# EEG_Schematic.net
KiCad netlist of a schematic drawn in Altium Designer
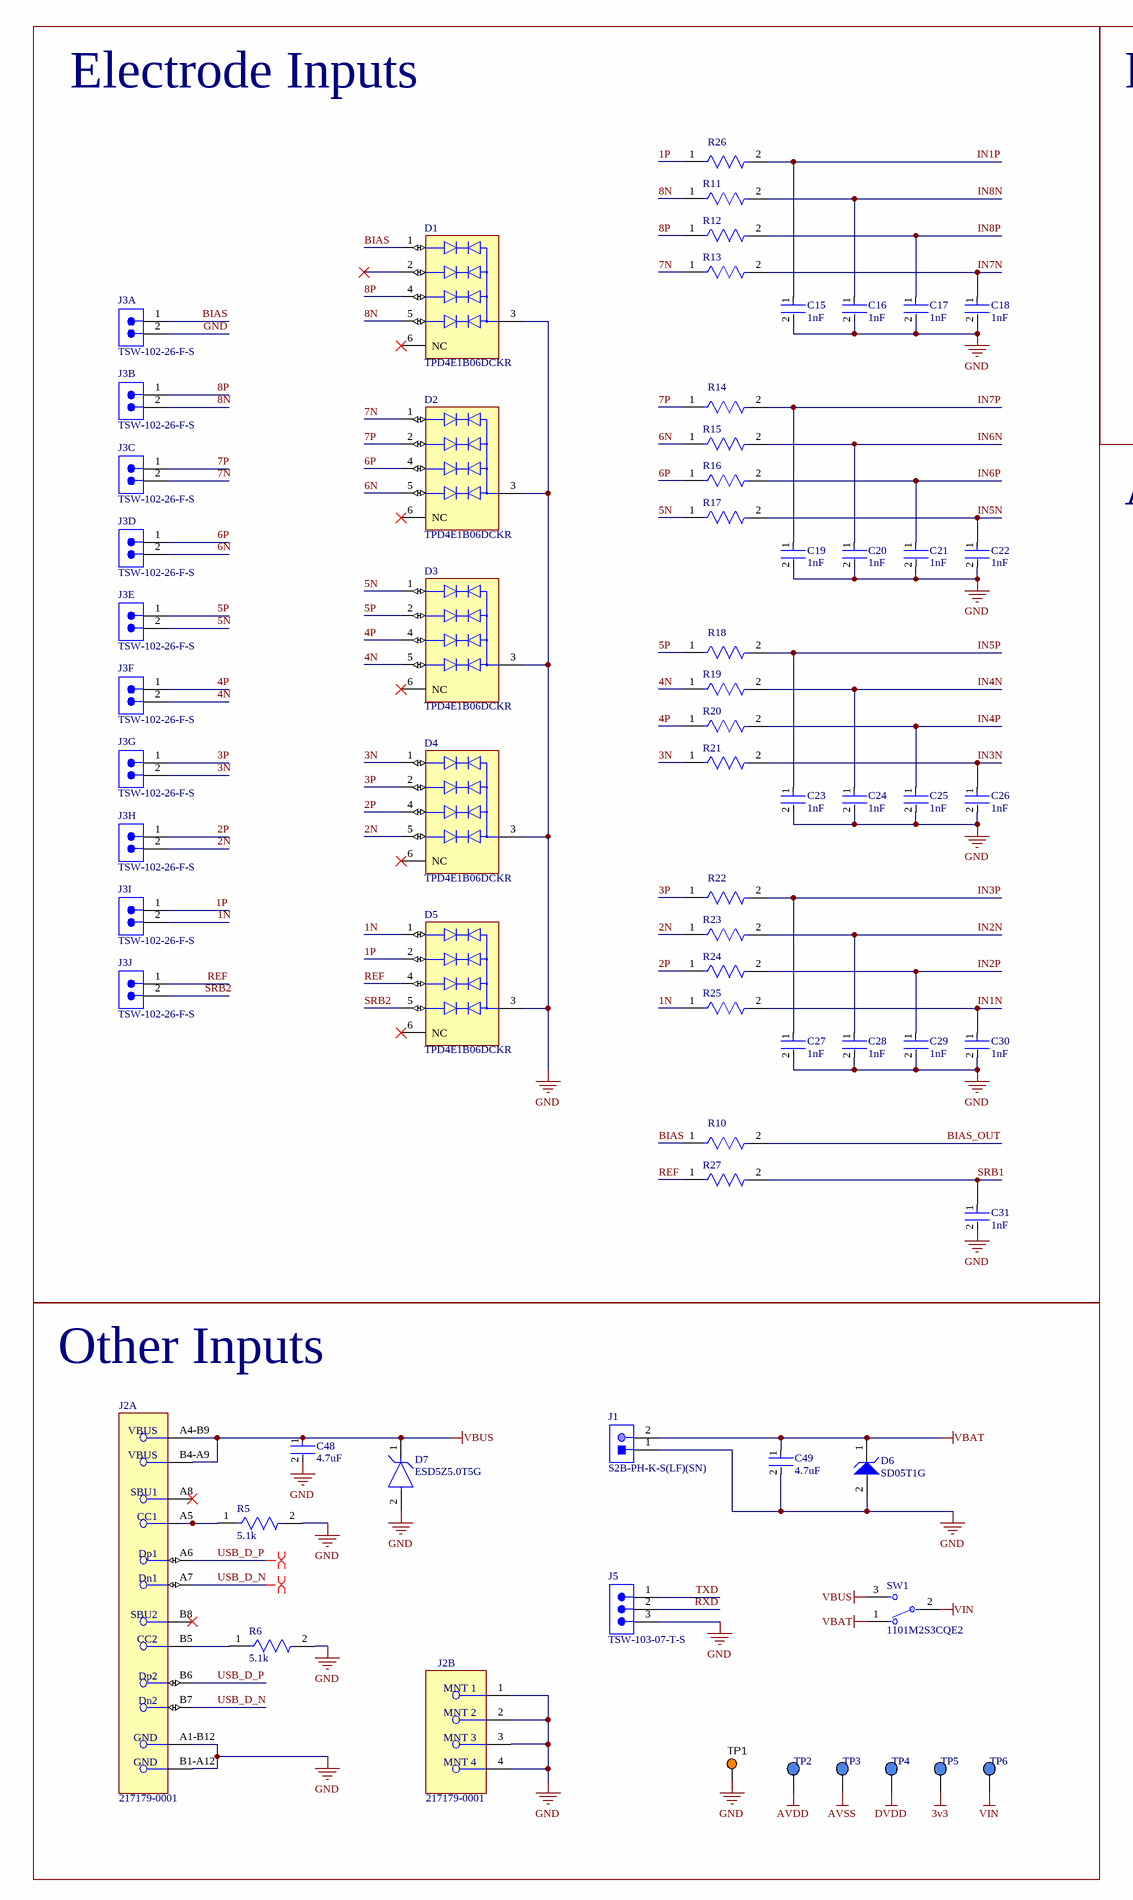
[diagram p0: EEG_Schematic.SchDoc, left]
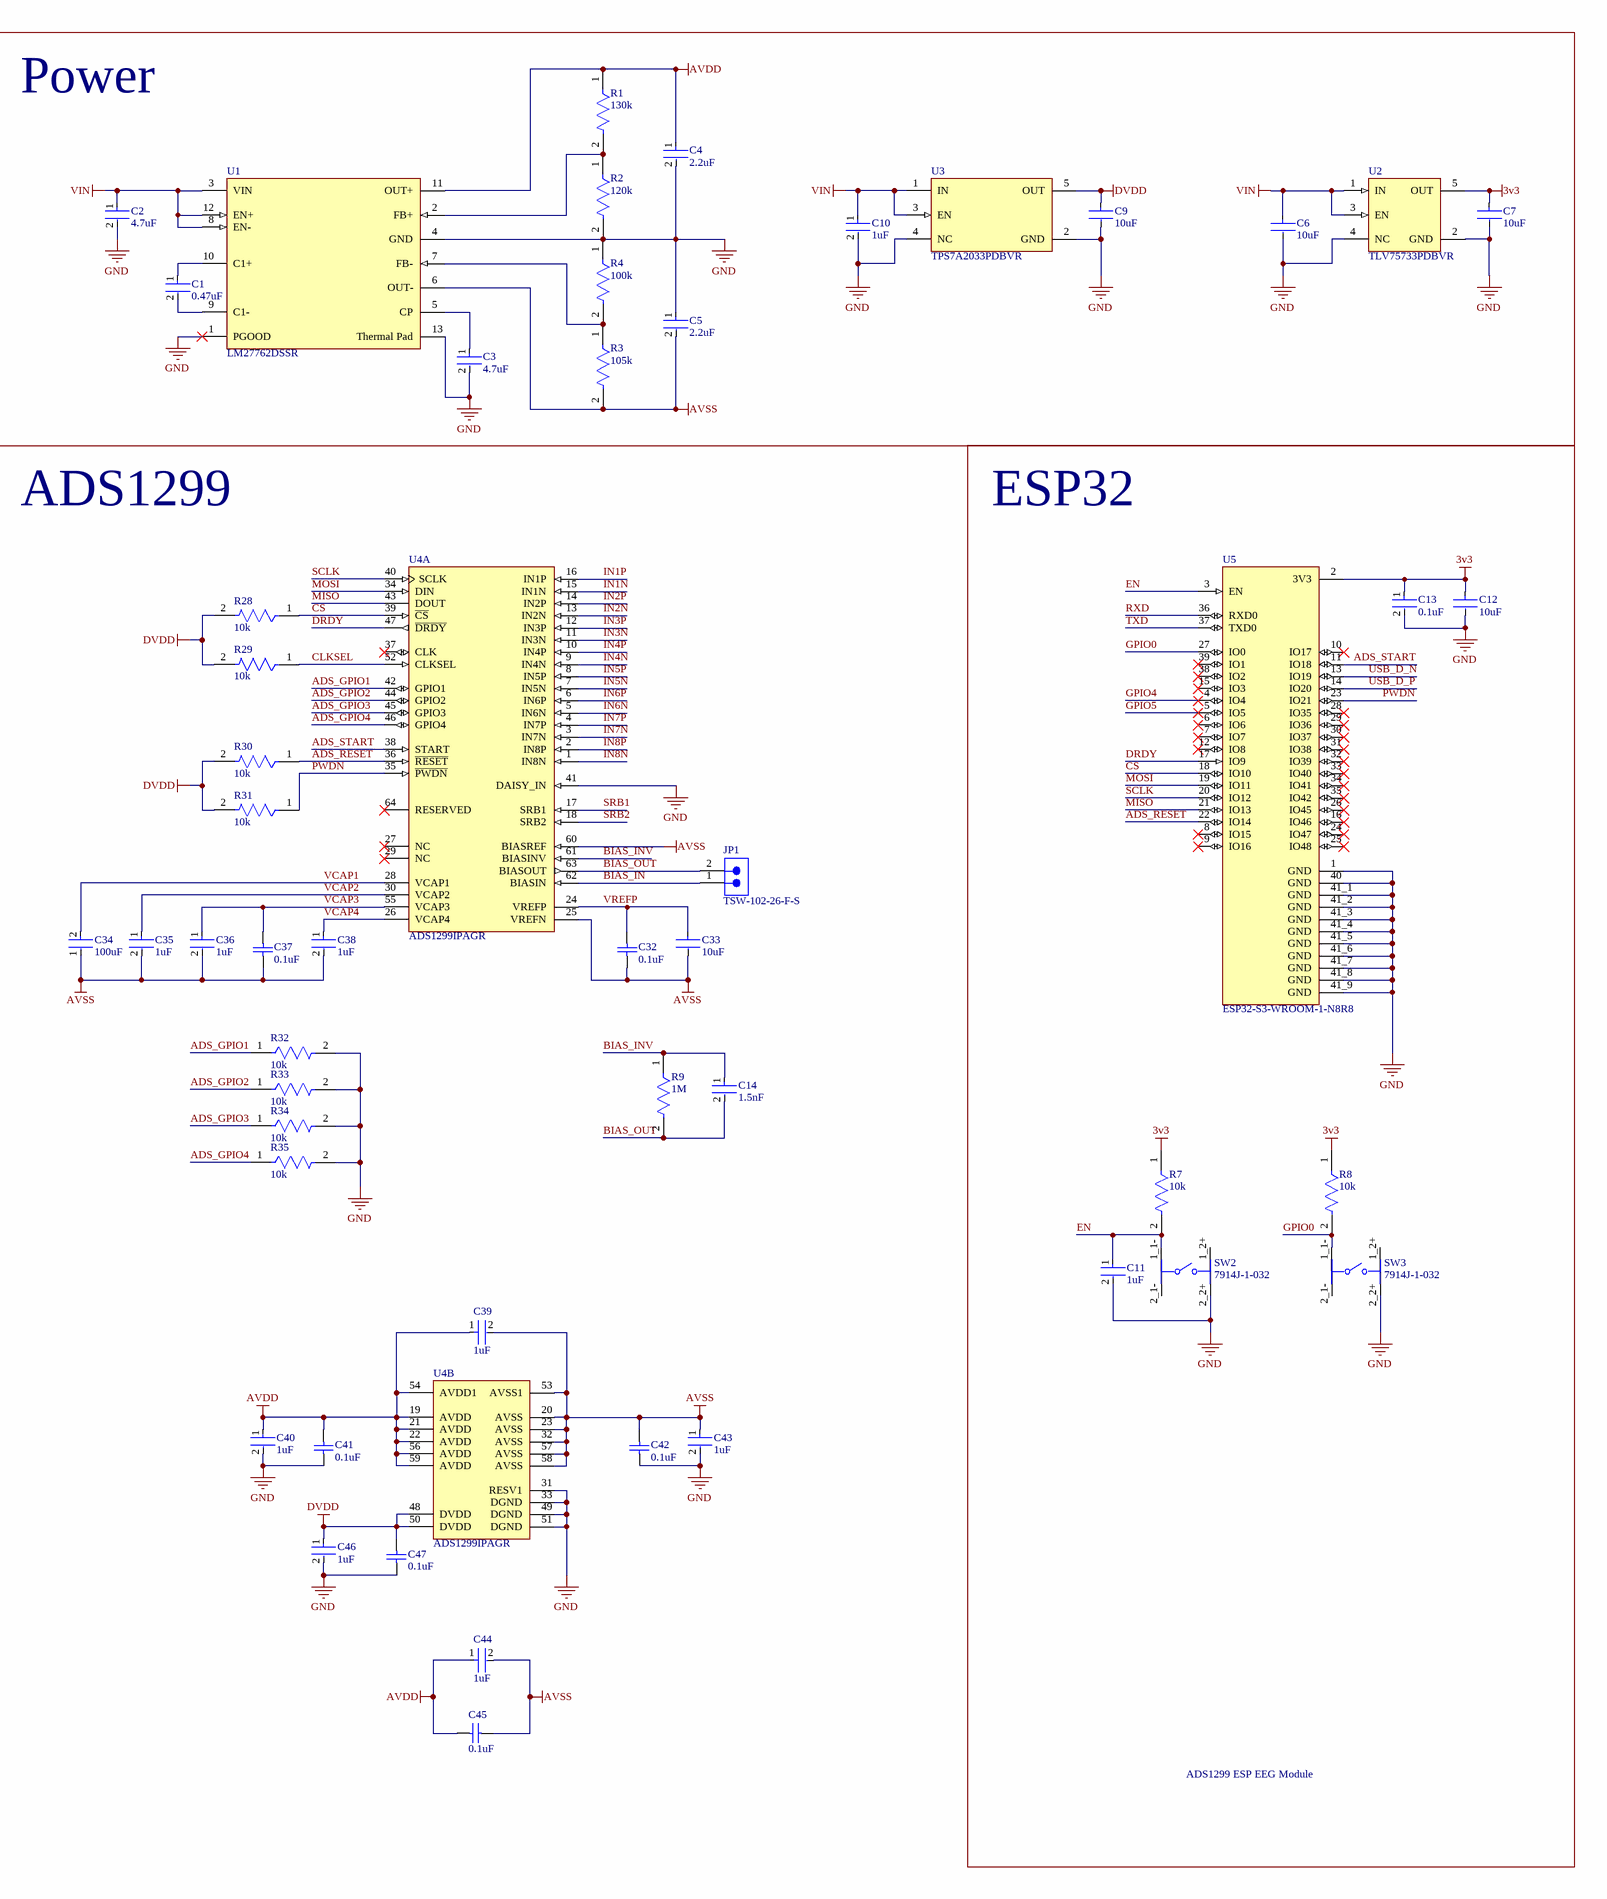
[diagram p1: EEG_Schematic.SchDoc, right]

(export (version "E")
  (design (tool "Eeschema 10.0.6"))
  (components
    (comp (ref "C1")
      (value "0.47uF")
      (footprint "FP-C0603C-CF-MFG")
      (description "Cap Ceramic 0.47uF 16V X7R 10% Pad SMD 0603 125C Automotive T/R")
      (fields (field (name "MANUFACTURER") "KEMET") (field (name "TOLERANCE") "0.1"))
      (libsource (lib "Altium Content Vault") (part "b4654b650e69147ec39a6b967a45e02"))
    )
    (comp (ref "C2")
      (value "4.7uF")
      (footprint "FP-GCJ21B-0_3-IPC_A")
      (description "Multilayer Ceramic Capacitors MLCC - SMD/SMT 0805 4.7uF 10%, 16VDC,  X7R 15%")
      (fields (field (name "TOLERANCE") "10%"))
      (libsource (lib "Altium Content Vault") (part "02cd4be3c70576c341d710602a673aa"))
    )
    (comp (ref "C3")
      (value "4.7uF")
      (footprint "FP-GCJ21B-0_3-IPC_A")
      (description "Multilayer Ceramic Capacitors MLCC - SMD/SMT 0805 4.7uF 10%, 16VDC,  X7R 15%")
      (fields (field (name "TOLERANCE") "10%"))
      (libsource (lib "Altium Content Vault") (part "02cd4be3c70576c341d710602a673aa"))
    )
    (comp (ref "C4")
      (value "2.2uF")
      (footprint "FP-GCM21B-0_15-IPC_B")
      (description "Ceramic Capacitor for Automotive 2.2uF ±10% 16VDC X7R 0805 Embossed T/R")
      (fields (field (name "TOLERANCE") "10%"))
      (libsource (lib "Altium Content Vault") (part "02cd4be3c70576c341d710602a673aa"))
    )
    (comp (ref "C5")
      (value "2.2uF")
      (footprint "FP-GCM21B-0_15-IPC_B")
      (description "Ceramic Capacitor for Automotive 2.2uF ±10% 16VDC X7R 0805 Embossed T/R")
      (fields (field (name "TOLERANCE") "10%"))
      (libsource (lib "Altium Content Vault") (part "02cd4be3c70576c341d710602a673aa"))
    )
    (comp (ref "C6")
      (value "10uF")
      (footprint "FP-GRJ21B-0_3-0_2-MFG")
      (description "CAP CER MLCC")
      (libsource (lib "") (part "11868f565c42a9108669ba33697ecf6_1"))
    )
    (comp (ref "C7")
      (value "10uF")
      (footprint "FP-GRJ21B-0_3-0_2-MFG")
      (description "CAP CER MLCC")
      (libsource (lib "") (part "11868f565c42a9108669ba33697ecf6_1"))
    )
    (comp (ref "C9")
      (value "10uF")
      (footprint "FP-GRJ21B-0_3-0_2-MFG")
      (description "CAP CER MLCC")
      (libsource (lib "") (part "11868f565c42a9108669ba33697ecf6_1"))
    )
    (comp (ref "C10")
      (value "1uF")
      (footprint "FP-CC0603-DA-MFG")
      (description "CAP CER 1UF 16V X7R 0603")
      (fields (field (name "TOLERANCE") "0.1") (field (name "MANUFACTURER") "YAGEO"))
      (libsource (lib "Altium Content Vault") (part "11868f565c42a9108669ba33697ecf6"))
    )
    (comp (ref "C11")
      (value "1uF")
      (footprint "FP-CC0603-DA-MFG")
      (description "CAP CER 1UF 16V X7R 0603")
      (fields (field (name "TOLERANCE") "0.1") (field (name "MANUFACTURER") "YAGEO"))
      (libsource (lib "Altium Content Vault") (part "11868f565c42a9108669ba33697ecf6"))
    )
    (comp (ref "C12")
      (value "10uF")
      (footprint "FP-GRJ21B-0_3-0_2-MFG")
      (description "CAP CER MLCC")
      (libsource (lib "") (part "11868f565c42a9108669ba33697ecf6_1"))
    )
    (comp (ref "C13")
      (value "0.1uF")
      (footprint "FP-CGA3E-0_3-0_1-MFG")
      (description "Cap Ceramic 100nF 50V X7R 10% Pad SMD 0603 +125°C Automotive T/R")
      (fields (field (name "TOLERANCE") "10%"))
      (libsource (lib "Altium Content Vault") (part "b4654b650e69147ec39a6b967a45e02"))
    )
    (comp (ref "C14")
      (value "1.5nF")
      (footprint "FP-C0603C-CF-MFG")
      (description "CAP CER 1500PF 100V NP0 0603")
      (fields
        (field (name "MANUFACTURER PART NUMBER") "C0603C152J1GACTU")
        (field (name "OCTOPART") "https://octopart.com/c0603c152j1gactu-kemet-12793172")
      )
      (libsource (lib "Altium Content Vault") (part "b4654b650e69147ec39a6b967a45e02"))
    )
    (comp (ref "C15")
      (value "1nF")
      (footprint "FP-C0603C-CF-MFG")
      (description "CAP CER 1000PF 50V 1% NP0 0603")
      (fields (field (name "TOLERANCE") "0.01") (field (name "MANUFACTURER PART NUMBER") "C0603C102F5GACTU"))
      (libsource (lib "Altium Content Vault") (part "b4654b650e69147ec39a6b967a45e02"))
    )
    (comp (ref "C16")
      (value "1nF")
      (footprint "FP-C0603C-CF-MFG")
      (description "CAP CER 1000PF 50V 1% NP0 0603")
      (fields (field (name "TOLERANCE") "0.01") (field (name "MANUFACTURER PART NUMBER") "C0603C102F5GACTU"))
      (libsource (lib "Altium Content Vault") (part "b4654b650e69147ec39a6b967a45e02"))
    )
    (comp (ref "C17")
      (value "1nF")
      (footprint "FP-C0603C-CF-MFG")
      (description "CAP CER 1000PF 50V 1% NP0 0603")
      (fields (field (name "TOLERANCE") "0.01") (field (name "MANUFACTURER PART NUMBER") "C0603C102F5GACTU"))
      (libsource (lib "Altium Content Vault") (part "b4654b650e69147ec39a6b967a45e02"))
    )
    (comp (ref "C18")
      (value "1nF")
      (footprint "FP-C0603C-CF-MFG")
      (description "CAP CER 1000PF 50V 1% NP0 0603")
      (fields (field (name "TOLERANCE") "0.01") (field (name "MANUFACTURER PART NUMBER") "C0603C102F5GACTU"))
      (libsource (lib "Altium Content Vault") (part "b4654b650e69147ec39a6b967a45e02"))
    )
    (comp (ref "C19")
      (value "1nF")
      (footprint "FP-C0603C-CF-MFG")
      (description "CAP CER 1000PF 50V 1% NP0 0603")
      (fields (field (name "TOLERANCE") "0.01") (field (name "MANUFACTURER PART NUMBER") "C0603C102F5GACTU"))
      (libsource (lib "Altium Content Vault") (part "b4654b650e69147ec39a6b967a45e02"))
    )
    (comp (ref "C20")
      (value "1nF")
      (footprint "FP-C0603C-CF-MFG")
      (description "CAP CER 1000PF 50V 1% NP0 0603")
      (fields (field (name "TOLERANCE") "0.01") (field (name "MANUFACTURER PART NUMBER") "C0603C102F5GACTU"))
      (libsource (lib "Altium Content Vault") (part "b4654b650e69147ec39a6b967a45e02"))
    )
    (comp (ref "C21")
      (value "1nF")
      (footprint "FP-C0603C-CF-MFG")
      (description "CAP CER 1000PF 50V 1% NP0 0603")
      (fields (field (name "TOLERANCE") "0.01") (field (name "MANUFACTURER PART NUMBER") "C0603C102F5GACTU"))
      (libsource (lib "Altium Content Vault") (part "b4654b650e69147ec39a6b967a45e02"))
    )
    (comp (ref "C22")
      (value "1nF")
      (footprint "FP-C0603C-CF-MFG")
      (description "CAP CER 1000PF 50V 1% NP0 0603")
      (fields (field (name "TOLERANCE") "0.01") (field (name "MANUFACTURER PART NUMBER") "C0603C102F5GACTU"))
      (libsource (lib "Altium Content Vault") (part "b4654b650e69147ec39a6b967a45e02"))
    )
    (comp (ref "C23")
      (value "1nF")
      (footprint "FP-C0603C-CF-MFG")
      (description "CAP CER 1000PF 50V 1% NP0 0603")
      (fields (field (name "TOLERANCE") "0.01") (field (name "MANUFACTURER PART NUMBER") "C0603C102F5GACTU"))
      (libsource (lib "Altium Content Vault") (part "b4654b650e69147ec39a6b967a45e02"))
    )
    (comp (ref "C24")
      (value "1nF")
      (footprint "FP-C0603C-CF-MFG")
      (description "CAP CER 1000PF 50V 1% NP0 0603")
      (fields (field (name "TOLERANCE") "0.01") (field (name "MANUFACTURER PART NUMBER") "C0603C102F5GACTU"))
      (libsource (lib "Altium Content Vault") (part "b4654b650e69147ec39a6b967a45e02"))
    )
    (comp (ref "C25")
      (value "1nF")
      (footprint "FP-C0603C-CF-MFG")
      (description "CAP CER 1000PF 50V 1% NP0 0603")
      (fields (field (name "TOLERANCE") "0.01") (field (name "MANUFACTURER PART NUMBER") "C0603C102F5GACTU"))
      (libsource (lib "Altium Content Vault") (part "b4654b650e69147ec39a6b967a45e02"))
    )
    (comp (ref "C26")
      (value "1nF")
      (footprint "FP-C0603C-CF-MFG")
      (description "CAP CER 1000PF 50V 1% NP0 0603")
      (fields (field (name "TOLERANCE") "0.01") (field (name "MANUFACTURER PART NUMBER") "C0603C102F5GACTU"))
      (libsource (lib "Altium Content Vault") (part "b4654b650e69147ec39a6b967a45e02"))
    )
    (comp (ref "C27")
      (value "1nF")
      (footprint "FP-C0603C-CF-MFG")
      (description "CAP CER 1000PF 50V 1% NP0 0603")
      (fields (field (name "TOLERANCE") "0.01") (field (name "MANUFACTURER PART NUMBER") "C0603C102F5GACTU"))
      (libsource (lib "Altium Content Vault") (part "b4654b650e69147ec39a6b967a45e02"))
    )
    (comp (ref "C28")
      (value "1nF")
      (footprint "FP-C0603C-CF-MFG")
      (description "CAP CER 1000PF 50V 1% NP0 0603")
      (fields (field (name "TOLERANCE") "0.01") (field (name "MANUFACTURER PART NUMBER") "C0603C102F5GACTU"))
      (libsource (lib "Altium Content Vault") (part "b4654b650e69147ec39a6b967a45e02"))
    )
    (comp (ref "C29")
      (value "1nF")
      (footprint "FP-C0603C-CF-MFG")
      (description "CAP CER 1000PF 50V 1% NP0 0603")
      (fields (field (name "TOLERANCE") "0.01") (field (name "MANUFACTURER PART NUMBER") "C0603C102F5GACTU"))
      (libsource (lib "Altium Content Vault") (part "b4654b650e69147ec39a6b967a45e02"))
    )
    (comp (ref "C30")
      (value "1nF")
      (footprint "FP-C0603C-CF-MFG")
      (description "CAP CER 1000PF 50V 1% NP0 0603")
      (fields (field (name "TOLERANCE") "0.01") (field (name "MANUFACTURER PART NUMBER") "C0603C102F5GACTU"))
      (libsource (lib "Altium Content Vault") (part "b4654b650e69147ec39a6b967a45e02"))
    )
    (comp (ref "C31")
      (value "1nF")
      (footprint "FP-C0603C-CF-MFG")
      (description "CAP CER 1000PF 50V 1% NP0 0603")
      (fields (field (name "TOLERANCE") "0.01") (field (name "MANUFACTURER PART NUMBER") "C0603C102F5GACTU"))
      (libsource (lib "Altium Content Vault") (part "b4654b650e69147ec39a6b967a45e02"))
    )
    (comp (ref "C32")
      (value "0.1uF")
      (footprint "CAPC1608X87X45LL20T05")
      (fields (field (name "PART NUMBER") "C0603X104J4RACTU") (field (name "MANUFACTURER") "Kemet"))
      (libsource (lib "Altium Content Vault") (part "CAP"))
    )
    (comp (ref "C33")
      (value "10uF")
      (footprint "FP-GRJ21B-0_3-0_2-MFG")
      (description "CAP CER MLCC")
      (libsource (lib "") (part "11868f565c42a9108669ba33697ecf6_1"))
    )
    (comp (ref "C34")
      (value "100uF")
      (footprint "FP-GRM31C-0_3-e0_3_0_8-IPC_B")
      (description "Chip Multilayer Ceramic Capacitors for General Purpose, 1206, 100uF, X5R, 15%, 20%, 10V")
      (libsource (lib "Altium Content Vault") (part "f23184f103b6ebe33a8c269c53dcba6"))
    )
    (comp (ref "C35")
      (value "1uF")
      (footprint "FP-CC0603-DA-MFG")
      (description "CAP CER 1UF 16V X7R 0603")
      (fields (field (name "TOLERANCE") "0.1") (field (name "MANUFACTURER") "YAGEO"))
      (libsource (lib "Altium Content Vault") (part "11868f565c42a9108669ba33697ecf6"))
    )
    (comp (ref "C36")
      (value "1uF")
      (footprint "FP-CC0603-DA-MFG")
      (description "CAP CER 1UF 16V X7R 0603")
      (fields (field (name "TOLERANCE") "0.1") (field (name "MANUFACTURER") "YAGEO"))
      (libsource (lib "Altium Content Vault") (part "11868f565c42a9108669ba33697ecf6"))
    )
    (comp (ref "C37")
      (value "0.1uF")
      (footprint "CAPC1608X87X45LL20T05")
      (fields (field (name "PART NUMBER") "C0603X104J4RACTU") (field (name "MANUFACTURER") "Kemet"))
      (libsource (lib "Altium Content Vault") (part "CAP"))
    )
    (comp (ref "C38")
      (value "1uF")
      (footprint "FP-CC0603-DA-MFG")
      (description "CAP CER 1UF 16V X7R 0603")
      (fields (field (name "TOLERANCE") "0.1") (field (name "MANUFACTURER") "YAGEO"))
      (libsource (lib "Altium Content Vault") (part "11868f565c42a9108669ba33697ecf6"))
    )
    (comp (ref "C39")
      (value "1uF")
      (footprint "FP-CC0603-DA-MFG")
      (description "CAP CER 1UF 16V X7R 0603")
      (fields (field (name "TOLERANCE") "0.1") (field (name "MANUFACTURER") "YAGEO"))
      (libsource (lib "Altium Content Vault") (part "11868f565c42a9108669ba33697ecf6"))
    )
    (comp (ref "C40")
      (value "1uF")
      (footprint "FP-CC0603-DA-MFG")
      (description "CAP CER 1UF 16V X7R 0603")
      (fields (field (name "TOLERANCE") "0.1") (field (name "MANUFACTURER") "YAGEO"))
      (libsource (lib "Altium Content Vault") (part "11868f565c42a9108669ba33697ecf6"))
    )
    (comp (ref "C41")
      (value "0.1uF")
      (footprint "CAPC1608X87X45LL20T05")
      (fields (field (name "PART NUMBER") "C0603X104J4RACTU") (field (name "MANUFACTURER") "Kemet"))
      (libsource (lib "Altium Content Vault") (part "CAP"))
    )
    (comp (ref "C42")
      (value "0.1uF")
      (footprint "CAPC1608X87X45LL20T05")
      (fields (field (name "PART NUMBER") "C0603X104J4RACTU") (field (name "MANUFACTURER") "Kemet"))
      (libsource (lib "Altium Content Vault") (part "CAP"))
    )
    (comp (ref "C43")
      (value "1uF")
      (footprint "FP-CC0603-DA-MFG")
      (description "CAP CER 1UF 16V X7R 0603")
      (fields (field (name "TOLERANCE") "0.1") (field (name "MANUFACTURER") "YAGEO"))
      (libsource (lib "Altium Content Vault") (part "11868f565c42a9108669ba33697ecf6"))
    )
    (comp (ref "C44")
      (value "1uF")
      (footprint "FP-CC0603-DA-MFG")
      (description "CAP CER 1UF 16V X7R 0603")
      (fields (field (name "TOLERANCE") "0.1") (field (name "MANUFACTURER") "YAGEO"))
      (libsource (lib "Altium Content Vault") (part "11868f565c42a9108669ba33697ecf6"))
    )
    (comp (ref "C45")
      (value "0.1uF")
      (footprint "CAPC1608X87X45LL20T05")
      (fields (field (name "PART NUMBER") "C0603X104J4RACTU") (field (name "MANUFACTURER") "Kemet"))
      (libsource (lib "Altium Content Vault") (part "CAP"))
    )
    (comp (ref "C46")
      (value "1uF")
      (footprint "FP-CC0603-DA-MFG")
      (description "CAP CER 1UF 16V X7R 0603")
      (fields (field (name "TOLERANCE") "0.1") (field (name "MANUFACTURER") "YAGEO"))
      (libsource (lib "Altium Content Vault") (part "11868f565c42a9108669ba33697ecf6"))
    )
    (comp (ref "C47")
      (value "0.1uF")
      (footprint "CAPC1608X87X45LL20T05")
      (fields (field (name "PART NUMBER") "C0603X104J4RACTU") (field (name "MANUFACTURER") "Kemet"))
      (libsource (lib "Altium Content Vault") (part "CAP"))
    )
    (comp (ref "C48")
      (value "4.7uF")
      (footprint "FP-GCJ21B-0_3-IPC_A")
      (description "Multilayer Ceramic Capacitors MLCC - SMD/SMT 0805 4.7uF 10%, 16VDC,  X7R 15%")
      (fields (field (name "TOLERANCE") "10%"))
      (libsource (lib "Altium Content Vault") (part "02cd4be3c70576c341d710602a673aa"))
    )
    (comp (ref "C49")
      (value "4.7uF")
      (footprint "FP-GCJ21B-0_3-IPC_A")
      (description "Multilayer Ceramic Capacitors MLCC - SMD/SMT 0805 4.7uF 10%, 16VDC,  X7R 15%")
      (fields (field (name "TOLERANCE") "10%"))
      (libsource (lib "Altium Content Vault") (part "02cd4be3c70576c341d710602a673aa"))
    )
    (comp (ref "D1")
      (value "TPD4E1B06DCKR")
      (footprint "TVS_TPD4E1B06DCKR")
      (description "Quad 0.7-pF, Â±5.5-V, Â±12-kV ESD protection diode with 0.5-nA max leakage in SOT & SC70 packages")
      (fields (field (name "MF") "Texas Instruments"))
      (libsource (lib "TPD4E1B06DCKR") (part "TPD4E1B06DCKR"))
    )
    (comp (ref "D2")
      (value "TPD4E1B06DCKR")
      (footprint "TVS_TPD4E1B06DCKR")
      (description "Quad 0.7-pF, Â±5.5-V, Â±12-kV ESD protection diode with 0.5-nA max leakage in SOT & SC70 packages")
      (fields (field (name "MF") "Texas Instruments"))
      (libsource (lib "TPD4E1B06DCKR") (part "TPD4E1B06DCKR"))
    )
    (comp (ref "D3")
      (value "TPD4E1B06DCKR")
      (footprint "TVS_TPD4E1B06DCKR")
      (description "Quad 0.7-pF, Â±5.5-V, Â±12-kV ESD protection diode with 0.5-nA max leakage in SOT & SC70 packages")
      (fields (field (name "MF") "Texas Instruments"))
      (libsource (lib "TPD4E1B06DCKR") (part "TPD4E1B06DCKR"))
    )
    (comp (ref "D4")
      (value "TPD4E1B06DCKR")
      (footprint "TVS_TPD4E1B06DCKR")
      (description "Quad 0.7-pF, Â±5.5-V, Â±12-kV ESD protection diode with 0.5-nA max leakage in SOT & SC70 packages")
      (fields (field (name "MF") "Texas Instruments"))
      (libsource (lib "TPD4E1B06DCKR") (part "TPD4E1B06DCKR"))
    )
    (comp (ref "D5")
      (value "TPD4E1B06DCKR")
      (footprint "TVS_TPD4E1B06DCKR")
      (description "Quad 0.7-pF, Â±5.5-V, Â±12-kV ESD protection diode with 0.5-nA max leakage in SOT & SC70 packages")
      (fields (field (name "MF") "Texas Instruments"))
      (libsource (lib "TPD4E1B06DCKR") (part "TPD4E1B06DCKR"))
    )
    (comp (ref "D6")
      (value "SD05T1G")
      (footprint "ONSC-SOD-323-2-477-02_G_V")
      (description "Transient Voltage Suppressor Diode, for ESD Protection, 2-Pin SOD-323, Pb-Free, Tape and Reel")
      (fields (field (name "MANUFACTURER") "On Semiconductor"))
      (libsource (lib "Altium Content Vault") (part "ONSC-K1A2-2"))
    )
    (comp (ref "D7")
      (value "ESD5Z5.0T5G")
      (footprint "FP-502-01-MFG")
      (description "ESD5Z5.0T5G Trans Voltage Suppressor Diode, 174W, 5V V(RWM), Unidirectional, 1 Element, Silicon")
      (libsource (lib "Altium Content Vault") (part "d9da4cfb8af32e832502365dfa3d88e"))
    )
    (comp (ref "J1")
      (value "S2B-PH-K-S(LF)(SN)")
      (footprint "JST-S2B-PH-K-S_V")
      (fields (field (name "TOLERANCE") "20%"))
      (libsource (lib "Altium Content Vault") (part "CN-1P-M-R2"))
    )
    (comp (ref "J2")
      (value "217179-0001")
      (footprint "FP-2171790001-MFG")
      (description "CONN RCP USB2.0 TYP C 24P SMD RA")
      (libsource (lib "Altium Content Vault") (part "8b86497a633d14b3f74642136fc0ce6"))
    )
    (comp (ref "J3A")
      (value "TSW-102-26-F-S")
      (footprint "SMTC-TSW-102-26-XX-S")
      (description "0.025\" SQ Post Header, Through-hole, Vertical, -55 to 125 degC, 2.54 mm Pitch, 2-Pin, Male, RoHS")
      (fields (field (name "MANUFACTURER") "Samtec"))
      (libsource (lib "Altium Content Vault") (part "SMTC-TSW-102-X-X-S-X"))
    )
    (comp (ref "J3B")
      (value "TSW-102-26-F-S")
      (footprint "SMTC-TSW-102-26-XX-S")
      (description "0.025\" SQ Post Header, Through-hole, Vertical, -55 to 125 degC, 2.54 mm Pitch, 2-Pin, Male, RoHS")
      (fields (field (name "MANUFACTURER") "Samtec"))
      (libsource (lib "Altium Content Vault") (part "SMTC-TSW-102-X-X-S-X"))
    )
    (comp (ref "J3C")
      (value "TSW-102-26-F-S")
      (footprint "SMTC-TSW-102-26-XX-S")
      (description "0.025\" SQ Post Header, Through-hole, Vertical, -55 to 125 degC, 2.54 mm Pitch, 2-Pin, Male, RoHS")
      (fields (field (name "MANUFACTURER") "Samtec"))
      (libsource (lib "Altium Content Vault") (part "SMTC-TSW-102-X-X-S-X"))
    )
    (comp (ref "J3D")
      (value "TSW-102-26-F-S")
      (footprint "SMTC-TSW-102-26-XX-S")
      (description "0.025\" SQ Post Header, Through-hole, Vertical, -55 to 125 degC, 2.54 mm Pitch, 2-Pin, Male, RoHS")
      (fields (field (name "MANUFACTURER") "Samtec"))
      (libsource (lib "Altium Content Vault") (part "SMTC-TSW-102-X-X-S-X"))
    )
    (comp (ref "J3E")
      (value "TSW-102-26-F-S")
      (footprint "SMTC-TSW-102-26-XX-S")
      (description "0.025\" SQ Post Header, Through-hole, Vertical, -55 to 125 degC, 2.54 mm Pitch, 2-Pin, Male, RoHS")
      (fields (field (name "MANUFACTURER") "Samtec"))
      (libsource (lib "Altium Content Vault") (part "SMTC-TSW-102-X-X-S-X"))
    )
    (comp (ref "J3F")
      (value "TSW-102-26-F-S")
      (footprint "SMTC-TSW-102-26-XX-S")
      (description "0.025\" SQ Post Header, Through-hole, Vertical, -55 to 125 degC, 2.54 mm Pitch, 2-Pin, Male, RoHS")
      (fields (field (name "MANUFACTURER") "Samtec"))
      (libsource (lib "Altium Content Vault") (part "SMTC-TSW-102-X-X-S-X"))
    )
    (comp (ref "J3G")
      (value "TSW-102-26-F-S")
      (footprint "SMTC-TSW-102-26-XX-S")
      (description "0.025\" SQ Post Header, Through-hole, Vertical, -55 to 125 degC, 2.54 mm Pitch, 2-Pin, Male, RoHS")
      (fields (field (name "MANUFACTURER") "Samtec"))
      (libsource (lib "Altium Content Vault") (part "SMTC-TSW-102-X-X-S-X"))
    )
    (comp (ref "J3H")
      (value "TSW-102-26-F-S")
      (footprint "SMTC-TSW-102-26-XX-S")
      (description "0.025\" SQ Post Header, Through-hole, Vertical, -55 to 125 degC, 2.54 mm Pitch, 2-Pin, Male, RoHS")
      (fields (field (name "MANUFACTURER") "Samtec"))
      (libsource (lib "Altium Content Vault") (part "SMTC-TSW-102-X-X-S-X"))
    )
    (comp (ref "J3I")
      (value "TSW-102-26-F-S")
      (footprint "SMTC-TSW-102-26-XX-S")
      (description "0.025\" SQ Post Header, Through-hole, Vertical, -55 to 125 degC, 2.54 mm Pitch, 2-Pin, Male, RoHS")
      (fields (field (name "MANUFACTURER") "Samtec"))
      (libsource (lib "Altium Content Vault") (part "SMTC-TSW-102-X-X-S-X"))
    )
    (comp (ref "J3J")
      (value "TSW-102-26-F-S")
      (footprint "SMTC-TSW-102-26-XX-S")
      (description "0.025\" SQ Post Header, Through-hole, Vertical, -55 to 125 degC, 2.54 mm Pitch, 2-Pin, Male, RoHS")
      (fields (field (name "MANUFACTURER") "Samtec"))
      (libsource (lib "Altium Content Vault") (part "SMTC-TSW-102-X-X-S-X"))
    )
    (comp (ref "J5")
      (value "TSW-103-07-T-S")
      (footprint "SMTC-TSW-103-07-X-S")
      (description "0.025\" SQ Post Header, Through-hole, Vertical, -55 to 105 degC, 2.54 mm Pitch, 3-Pin, Male, RoHS")
      (fields (field (name "MANUFACTURER") "Samtec"))
      (libsource (lib "Altium Content Vault") (part "SMTC-TSW-103-X-X-S-X"))
    )
    (comp (ref "JP1")
      (value "TSW-102-26-F-S")
      (footprint "SMTC-TSW-102-26-XX-S")
      (description "0.025\" SQ Post Header, Through-hole, Vertical, -55 to 125 degC, 2.54 mm Pitch, 2-Pin, Male, RoHS")
      (fields (field (name "MANUFACTURER") "Samtec"))
      (libsource (lib "Altium Content Vault") (part "SMTC-TSW-102-X-X-S-X"))
    )
    (comp (ref "R1")
      (value "130k")
      (footprint "FP-MCT0603-IPC_B")
      (description "RES SMD 100 OHM 1% 1/8W 0603")
      (fields (field (name "TOLERANCE") "0.1%"))
      (libsource (lib "Altium Content Vault") (part "1029c3af85768c4190bb7ad29bc67b5"))
    )
    (comp (ref "R2")
      (value "120k")
      (footprint "FP-RT0603-MFG")
      (description "RES SMD 120K OHM 0.1% 1/10W 0603")
      (fields (field (name "TOLERANCE") "0.001") (field (name "MANUFACTURER") "Yageo"))
      (libsource (lib "Altium Content Vault") (part "1029c3af85768c4190bb7ad29bc67b5"))
    )
    (comp (ref "R3")
      (value "105k")
      (footprint "FP-RT0603-MFG")
      (description "RES SMD 105K OHM 0.1% 1/10W 0603")
      (fields
        (field (name "MANUFACTURER PART NUMBER") "RT0603BRD07105KL")
        (field (name "OCTOPART") "https://octopart.com/rt0603brd07105kl-yageo-1216175")
      )
      (libsource (lib "Altium Content Vault") (part "1029c3af85768c4190bb7ad29bc67b5"))
    )
    (comp (ref "R4")
      (value "100k")
      (footprint "FP-AT0603-IPC_A")
      (description "Thin Film Chip Resistors Automotive Grade 100kΩ 0.1% 25ppm/°C 0603")
      (fields (field (name "TOLERANCE") "0.1%"))
      (libsource (lib "Altium Content Vault") (part "1029c3af85768c4190bb7ad29bc67b5"))
    )
    (comp (ref "R5")
      (value "5.1k")
      (footprint "FP-RT0603-MFG")
      (description "RES SMD 5.1K OHM 1% 1/10W 0603")
      (fields
        (field (name "MANUFACTURER") "Yageo")
        (field (name "OCTOPART") "https://octopart.com/rt0603fre075k1l-yageo-1421390")
      )
      (libsource (lib "Altium Content Vault") (part "1029c3af85768c4190bb7ad29bc67b5"))
    )
    (comp (ref "R6")
      (value "5.1k")
      (footprint "FP-RT0603-MFG")
      (description "RES SMD 5.1K OHM 1% 1/10W 0603")
      (fields
        (field (name "MANUFACTURER") "Yageo")
        (field (name "OCTOPART") "https://octopart.com/rt0603fre075k1l-yageo-1421390")
      )
      (libsource (lib "Altium Content Vault") (part "1029c3af85768c4190bb7ad29bc67b5"))
    )
    (comp (ref "R7")
      (value "10k")
      (footprint "FP-AC0603-MFG")
      (description "RES 10kΩ 1.00% 0.2W 0603")
      (libsource (lib "Altium Content Vault") (part "1029c3af85768c4190bb7ad29bc67b5"))
    )
    (comp (ref "R8")
      (value "10k")
      (footprint "FP-AC0603-MFG")
      (description "RES 10kΩ 1.00% 0.2W 0603")
      (libsource (lib "Altium Content Vault") (part "1029c3af85768c4190bb7ad29bc67b5"))
    )
    (comp (ref "R9")
      (value "1M")
      (footprint "FP-MCT0603-MFG")
      (description "RES SMD 100 OHM 1% 1/8W 0603")
      (fields (field (name "TOLERANCE") "1%"))
      (libsource (lib "Altium Content Vault") (part "1029c3af85768c4190bb7ad29bc67b5"))
    )
    (comp (ref "R10")
      (value "2.2k")
      (footprint "FP-MCT0603-IPC_A")
      (description "RES SMD 100 OHM 1% 1/8W 0603")
      (fields (field (name "TOLERANCE") "0.1%"))
      (libsource (lib "Altium Content Vault") (part "1029c3af85768c4190bb7ad29bc67b5"))
    )
    (comp (ref "R11")
      (value "2.2k")
      (footprint "FP-MCT0603-IPC_A")
      (description "RES SMD 100 OHM 1% 1/8W 0603")
      (fields (field (name "TOLERANCE") "0.1%"))
      (libsource (lib "Altium Content Vault") (part "1029c3af85768c4190bb7ad29bc67b5"))
    )
    (comp (ref "R12")
      (value "2.2k")
      (footprint "FP-MCT0603-IPC_A")
      (description "RES SMD 100 OHM 1% 1/8W 0603")
      (fields (field (name "TOLERANCE") "0.1%"))
      (libsource (lib "Altium Content Vault") (part "1029c3af85768c4190bb7ad29bc67b5"))
    )
    (comp (ref "R13")
      (value "2.2k")
      (footprint "FP-MCT0603-IPC_A")
      (description "RES SMD 100 OHM 1% 1/8W 0603")
      (fields (field (name "TOLERANCE") "0.1%"))
      (libsource (lib "Altium Content Vault") (part "1029c3af85768c4190bb7ad29bc67b5"))
    )
    (comp (ref "R14")
      (value "2.2k")
      (footprint "FP-MCT0603-IPC_A")
      (description "RES SMD 100 OHM 1% 1/8W 0603")
      (fields (field (name "TOLERANCE") "0.1%"))
      (libsource (lib "Altium Content Vault") (part "1029c3af85768c4190bb7ad29bc67b5"))
    )
    (comp (ref "R15")
      (value "2.2k")
      (footprint "FP-MCT0603-IPC_A")
      (description "RES SMD 100 OHM 1% 1/8W 0603")
      (fields (field (name "TOLERANCE") "0.1%"))
      (libsource (lib "Altium Content Vault") (part "1029c3af85768c4190bb7ad29bc67b5"))
    )
    (comp (ref "R16")
      (value "2.2k")
      (footprint "FP-MCT0603-IPC_A")
      (description "RES SMD 100 OHM 1% 1/8W 0603")
      (fields (field (name "TOLERANCE") "0.1%"))
      (libsource (lib "Altium Content Vault") (part "1029c3af85768c4190bb7ad29bc67b5"))
    )
    (comp (ref "R17")
      (value "2.2k")
      (footprint "FP-MCT0603-IPC_A")
      (description "RES SMD 100 OHM 1% 1/8W 0603")
      (fields (field (name "TOLERANCE") "0.1%"))
      (libsource (lib "Altium Content Vault") (part "1029c3af85768c4190bb7ad29bc67b5"))
    )
    (comp (ref "R18")
      (value "2.2k")
      (footprint "FP-MCT0603-IPC_A")
      (description "RES SMD 100 OHM 1% 1/8W 0603")
      (fields (field (name "TOLERANCE") "0.1%"))
      (libsource (lib "Altium Content Vault") (part "1029c3af85768c4190bb7ad29bc67b5"))
    )
    (comp (ref "R19")
      (value "2.2k")
      (footprint "FP-MCT0603-IPC_A")
      (description "RES SMD 100 OHM 1% 1/8W 0603")
      (fields (field (name "TOLERANCE") "0.1%"))
      (libsource (lib "Altium Content Vault") (part "1029c3af85768c4190bb7ad29bc67b5"))
    )
    (comp (ref "R20")
      (value "2.2k")
      (footprint "FP-MCT0603-IPC_A")
      (description "RES SMD 100 OHM 1% 1/8W 0603")
      (fields (field (name "TOLERANCE") "0.1%"))
      (libsource (lib "Altium Content Vault") (part "1029c3af85768c4190bb7ad29bc67b5"))
    )
    (comp (ref "R21")
      (value "2.2k")
      (footprint "FP-MCT0603-IPC_A")
      (description "RES SMD 100 OHM 1% 1/8W 0603")
      (fields (field (name "TOLERANCE") "0.1%"))
      (libsource (lib "Altium Content Vault") (part "1029c3af85768c4190bb7ad29bc67b5"))
    )
    (comp (ref "R22")
      (value "2.2k")
      (footprint "FP-MCT0603-IPC_A")
      (description "RES SMD 100 OHM 1% 1/8W 0603")
      (fields (field (name "TOLERANCE") "0.1%"))
      (libsource (lib "Altium Content Vault") (part "1029c3af85768c4190bb7ad29bc67b5"))
    )
    (comp (ref "R23")
      (value "2.2k")
      (footprint "FP-MCT0603-IPC_A")
      (description "RES SMD 100 OHM 1% 1/8W 0603")
      (fields (field (name "TOLERANCE") "0.1%"))
      (libsource (lib "Altium Content Vault") (part "1029c3af85768c4190bb7ad29bc67b5"))
    )
    (comp (ref "R24")
      (value "2.2k")
      (footprint "FP-MCT0603-IPC_A")
      (description "RES SMD 100 OHM 1% 1/8W 0603")
      (fields (field (name "TOLERANCE") "0.1%"))
      (libsource (lib "Altium Content Vault") (part "1029c3af85768c4190bb7ad29bc67b5"))
    )
    (comp (ref "R25")
      (value "2.2k")
      (footprint "FP-MCT0603-IPC_A")
      (description "RES SMD 100 OHM 1% 1/8W 0603")
      (fields (field (name "TOLERANCE") "0.1%"))
      (libsource (lib "Altium Content Vault") (part "1029c3af85768c4190bb7ad29bc67b5"))
    )
    (comp (ref "R26")
      (value "2.2k")
      (footprint "FP-MCT0603-IPC_A")
      (description "RES SMD 100 OHM 1% 1/8W 0603")
      (fields (field (name "TOLERANCE") "0.1%"))
      (libsource (lib "Altium Content Vault") (part "1029c3af85768c4190bb7ad29bc67b5"))
    )
    (comp (ref "R27")
      (value "2.2k")
      (footprint "FP-MCT0603-IPC_A")
      (description "RES SMD 100 OHM 1% 1/8W 0603")
      (fields (field (name "TOLERANCE") "0.1%"))
      (libsource (lib "Altium Content Vault") (part "1029c3af85768c4190bb7ad29bc67b5"))
    )
    (comp (ref "R28")
      (value "10k")
      (footprint "FP-AC0603-MFG")
      (description "RES 10kΩ 1.00% 0.2W 0603")
      (libsource (lib "Altium Content Vault") (part "1029c3af85768c4190bb7ad29bc67b5"))
    )
    (comp (ref "R29")
      (value "10k")
      (footprint "FP-AC0603-MFG")
      (description "RES 10kΩ 1.00% 0.2W 0603")
      (libsource (lib "Altium Content Vault") (part "1029c3af85768c4190bb7ad29bc67b5"))
    )
    (comp (ref "R30")
      (value "10k")
      (footprint "FP-AC0603-MFG")
      (description "RES 10kΩ 1.00% 0.2W 0603")
      (libsource (lib "Altium Content Vault") (part "1029c3af85768c4190bb7ad29bc67b5"))
    )
    (comp (ref "R31")
      (value "10k")
      (footprint "FP-AC0603-MFG")
      (description "RES 10kΩ 1.00% 0.2W 0603")
      (libsource (lib "Altium Content Vault") (part "1029c3af85768c4190bb7ad29bc67b5"))
    )
    (comp (ref "R32")
      (value "10k")
      (footprint "FP-AC0603-MFG")
      (description "RES 10kΩ 1.00% 0.2W 0603")
      (libsource (lib "Altium Content Vault") (part "1029c3af85768c4190bb7ad29bc67b5"))
    )
    (comp (ref "R33")
      (value "10k")
      (footprint "FP-AC0603-MFG")
      (description "RES 10kΩ 1.00% 0.2W 0603")
      (libsource (lib "Altium Content Vault") (part "1029c3af85768c4190bb7ad29bc67b5"))
    )
    (comp (ref "R34")
      (value "10k")
      (footprint "FP-AC0603-MFG")
      (description "RES 10kΩ 1.00% 0.2W 0603")
      (libsource (lib "Altium Content Vault") (part "1029c3af85768c4190bb7ad29bc67b5"))
    )
    (comp (ref "R35")
      (value "10k")
      (footprint "FP-AC0603-MFG")
      (description "RES 10kΩ 1.00% 0.2W 0603")
      (libsource (lib "Altium Content Vault") (part "1029c3af85768c4190bb7ad29bc67b5"))
    )
    (comp (ref "SW1")
      (value "1101M2S3CQE2")
      (footprint "FP-1101M2S3CQE2-MFG")
      (description "SWITCH SLIDE SPDT 6A 120V")
      (libsource (lib "Altium Content Vault") (part "7fcaa069a19c2acd609832313418d7c"))
    )
    (comp (ref "SW2")
      (value "7914J-1-032")
      (footprint "FP-7914J-1-032-MFG")
      (description "SWITCH TACTILE SPST-NO 0.1A 16V")
      (libsource (lib "Altium Content Vault") (part "31b61e1575766857d5d37af9ed38f2e"))
    )
    (comp (ref "SW3")
      (value "7914J-1-032")
      (footprint "FP-7914J-1-032-MFG")
      (description "SWITCH TACTILE SPST-NO 0.1A 16V")
      (libsource (lib "Altium Content Vault") (part "31b61e1575766857d5d37af9ed38f2e"))
    )
    (comp (ref "TP1")
      (value "~")
      (footprint "KSTN-5003")
      (description "Test Point, Orange, 1-Pin THD, RoHS")
      (libsource (lib "Altium Content Vault") (part "TESTPOINT_ORANGE"))
    )
    (comp (ref "TP2")
      (value "TP")
      (footprint "TP_SMD_2mm")
      (description "2mm diameter circular test point,")
      (libsource (lib "Test_Points") (part "TestPoint_SMD"))
    )
    (comp (ref "TP3")
      (value "TP")
      (footprint "TP_SMD_2mm")
      (description "2mm diameter circular test point,")
      (libsource (lib "Test_Points") (part "TestPoint_SMD"))
    )
    (comp (ref "TP4")
      (value "TP")
      (footprint "TP_SMD_2mm")
      (description "2mm diameter circular test point,")
      (libsource (lib "Test_Points") (part "TestPoint_SMD"))
    )
    (comp (ref "TP5")
      (value "TP")
      (footprint "TP_SMD_2mm")
      (description "2mm diameter circular test point,")
      (libsource (lib "Test_Points") (part "TestPoint_SMD"))
    )
    (comp (ref "TP6")
      (value "TP")
      (footprint "TP_SMD_2mm")
      (description "2mm diameter circular test point,")
      (libsource (lib "Test_Points") (part "TestPoint_SMD"))
    )
    (comp (ref "U1")
      (value "LM27762DSSR")
      (footprint "FP-DSS0012B-MFG")
      (description "IC REG CHARGE PUMP ADJ DL 12WSON")
      (libsource (lib "Altium Content Vault") (part "ab275a4f98ccada617dcf409ec46a20"))
    )
    (comp (ref "U2")
      (value "TLV75733PDBVR")
      (footprint "FP-DBV0005A-MFG")
      (description "IC REG LINEAR 3.3V 1A SOT23-5")
      (fields
        (field (name "MANUFACTURER") "Texas Instruments")
        (field (name "OCTOPART") "https://octopart.com/tlv75733pdbvr-texas+instruments-91437073")
      )
      (libsource (lib "Altium Content Vault") (part "0cbbc1df71e5372cce39b1d408f1f92"))
    )
    (comp (ref "U3")
      (value "TPS7A2033PDBVR")
      (footprint "FP-DBV0005A-MFG")
      (description "IC REG LINEAR 3.3V 300MA SOT23-5")
      (libsource (lib "Altium Content Vault") (part "76aa7ad0ceb1012e0d85aeafc53095f"))
    )
    (comp (ref "U4")
      (value "ADS1299IPAGR")
      (footprint "PAG0064A_M")
      (fields (field (name "MANUFACTURER") "Texas Instruments"))
      (libsource (lib "Altium Content Vault") (part "TI-ADS1299-PAG-64"))
    )
    (comp (ref "U5")
      (value "ESP32-S3-WROOM-1-N8R8")
      (footprint "XCVR_ESP32S3WROOM1N8R8")
      (description "Bluetooth, WiFi 802.11b/g/n, Bluetooth v5.0 Transceiver Module 2.4GHz PCB Trace Surface Mount")
      (fields (field (name "MF") "Espressif Systems"))
      (libsource (lib "ESP32-S3-WROOM-1-N8R8") (part "ESP32-S3-WROOM-1-N8R8"))
    )
  )
  (nets
    (net (code "1") (name "/1N") (class "Default")
      (node (ref "D5") (pin "1") (pinfunction "IO1_1") (pintype "bidirectional"))
      (node (ref "J3I") (pin "2") (pinfunction "2_2") (pintype "passive"))
      (node (ref "R25") (pin "1") (pinfunction "1_1") (pintype "passive"))
    )
    (net (code "2") (name "/1P") (class "Default")
      (node (ref "D5") (pin "2") (pinfunction "IO2_2") (pintype "bidirectional"))
      (node (ref "J3I") (pin "1") (pinfunction "1_1") (pintype "passive"))
      (node (ref "R26") (pin "1") (pinfunction "1_1") (pintype "passive"))
    )
    (net (code "3") (name "/2N") (class "Default")
      (node (ref "D4") (pin "5") (pinfunction "IO4_5") (pintype "bidirectional"))
      (node (ref "J3H") (pin "2") (pinfunction "2_2") (pintype "passive"))
      (node (ref "R23") (pin "1") (pinfunction "1_1") (pintype "passive"))
    )
    (net (code "4") (name "/2P") (class "Default")
      (node (ref "D4") (pin "4") (pinfunction "IO3_4") (pintype "bidirectional"))
      (node (ref "J3H") (pin "1") (pinfunction "1_1") (pintype "passive"))
      (node (ref "R24") (pin "1") (pinfunction "1_1") (pintype "passive"))
    )
    (net (code "5") (name "/3N") (class "Default")
      (node (ref "D4") (pin "1") (pinfunction "IO1_1") (pintype "bidirectional"))
      (node (ref "J3G") (pin "2") (pinfunction "2_2") (pintype "passive"))
      (node (ref "R21") (pin "1") (pinfunction "1_1") (pintype "passive"))
    )
    (net (code "6") (name "/3P") (class "Default")
      (node (ref "D4") (pin "2") (pinfunction "IO2_2") (pintype "bidirectional"))
      (node (ref "J3G") (pin "1") (pinfunction "1_1") (pintype "passive"))
      (node (ref "R22") (pin "1") (pinfunction "1_1") (pintype "passive"))
    )
    (net (code "7") (name "/4N") (class "Default")
      (node (ref "D3") (pin "5") (pinfunction "IO4_5") (pintype "bidirectional"))
      (node (ref "J3F") (pin "2") (pinfunction "2_2") (pintype "passive"))
      (node (ref "R19") (pin "1") (pinfunction "1_1") (pintype "passive"))
    )
    (net (code "8") (name "/4P") (class "Default")
      (node (ref "D3") (pin "4") (pinfunction "IO3_4") (pintype "bidirectional"))
      (node (ref "J3F") (pin "1") (pinfunction "1_1") (pintype "passive"))
      (node (ref "R20") (pin "1") (pinfunction "1_1") (pintype "passive"))
    )
    (net (code "9") (name "/5N") (class "Default")
      (node (ref "D3") (pin "1") (pinfunction "IO1_1") (pintype "bidirectional"))
      (node (ref "J3E") (pin "2") (pinfunction "2_2") (pintype "passive"))
      (node (ref "R17") (pin "1") (pinfunction "1_1") (pintype "passive"))
    )
    (net (code "10") (name "/5P") (class "Default")
      (node (ref "D3") (pin "2") (pinfunction "IO2_2") (pintype "bidirectional"))
      (node (ref "J3E") (pin "1") (pinfunction "1_1") (pintype "passive"))
      (node (ref "R18") (pin "1") (pinfunction "1_1") (pintype "passive"))
    )
    (net (code "11") (name "/6N") (class "Default")
      (node (ref "D2") (pin "5") (pinfunction "IO4_5") (pintype "bidirectional"))
      (node (ref "J3D") (pin "2") (pinfunction "2_2") (pintype "passive"))
      (node (ref "R15") (pin "1") (pinfunction "1_1") (pintype "passive"))
    )
    (net (code "12") (name "/6P") (class "Default")
      (node (ref "D2") (pin "4") (pinfunction "IO3_4") (pintype "bidirectional"))
      (node (ref "J3D") (pin "1") (pinfunction "1_1") (pintype "passive"))
      (node (ref "R16") (pin "1") (pinfunction "1_1") (pintype "passive"))
    )
    (net (code "13") (name "/7N") (class "Default")
      (node (ref "D2") (pin "1") (pinfunction "IO1_1") (pintype "bidirectional"))
      (node (ref "J3C") (pin "2") (pinfunction "2_2") (pintype "passive"))
      (node (ref "R13") (pin "1") (pinfunction "1_1") (pintype "passive"))
    )
    (net (code "14") (name "/7P") (class "Default")
      (node (ref "D2") (pin "2") (pinfunction "IO2_2") (pintype "bidirectional"))
      (node (ref "J3C") (pin "1") (pinfunction "1_1") (pintype "passive"))
      (node (ref "R14") (pin "1") (pinfunction "1_1") (pintype "passive"))
    )
    (net (code "15") (name "/8N") (class "Default")
      (node (ref "D1") (pin "5") (pinfunction "IO4_5") (pintype "bidirectional"))
      (node (ref "J3B") (pin "2") (pinfunction "2_2") (pintype "passive"))
      (node (ref "R11") (pin "1") (pinfunction "1_1") (pintype "passive"))
    )
    (net (code "16") (name "/8P") (class "Default")
      (node (ref "D1") (pin "4") (pinfunction "IO3_4") (pintype "bidirectional"))
      (node (ref "J3B") (pin "1") (pinfunction "1_1") (pintype "passive"))
      (node (ref "R12") (pin "1") (pinfunction "1_1") (pintype "passive"))
    )
    (net (code "17") (name "/ADS_GPIO1") (class "Default")
      (node (ref "R32") (pin "1") (pinfunction "1_1") (pintype "passive"))
      (node (ref "U4") (pin "42") (pinfunction "GPIO1_42") (pintype "bidirectional"))
    )
    (net (code "18") (name "/ADS_GPIO2") (class "Default")
      (node (ref "R33") (pin "1") (pinfunction "1_1") (pintype "passive"))
      (node (ref "U4") (pin "44") (pinfunction "GPIO2_44") (pintype "bidirectional"))
    )
    (net (code "19") (name "/ADS_GPIO3") (class "Default")
      (node (ref "R34") (pin "1") (pinfunction "1_1") (pintype "passive"))
      (node (ref "U4") (pin "45") (pinfunction "GPIO3_45") (pintype "bidirectional"))
    )
    (net (code "20") (name "/ADS_GPIO4") (class "Default")
      (node (ref "R35") (pin "1") (pinfunction "1_1") (pintype "passive"))
      (node (ref "U4") (pin "46") (pinfunction "GPIO4_46") (pintype "bidirectional"))
    )
    (net (code "21") (name "/ADS_RESET") (class "Default")
      (node (ref "R30") (pin "1") (pinfunction "1_1") (pintype "passive"))
      (node (ref "U4") (pin "36") (pinfunction "~{RESET}_36") (pintype "input"))
      (node (ref "U5") (pin "22") (pinfunction "IO14_22") (pintype "bidirectional"))
    )
    (net (code "22") (name "/ADS_START") (class "Default")
      (node (ref "U4") (pin "38") (pinfunction "START_38") (pintype "input"))
      (node (ref "U5") (pin "11") (pinfunction "IO18_11") (pintype "bidirectional"))
    )
    (net (code "23") (name "/BIAS") (class "Default")
      (node (ref "D1") (pin "1") (pinfunction "IO1_1") (pintype "bidirectional"))
      (node (ref "J3A") (pin "1") (pinfunction "1_1") (pintype "passive"))
      (node (ref "R10") (pin "1") (pinfunction "1_1") (pintype "passive"))
    )
    (net (code "24") (name "/BIAS_IN") (class "Default")
      (node (ref "JP1") (pin "1") (pinfunction "1_1") (pintype "passive"))
      (node (ref "U4") (pin "62") (pinfunction "BIASIN_62") (pintype "input"))
    )
    (net (code "25") (name "/BIAS_INV") (class "Default")
      (node (ref "C14") (pin "1") (pinfunction "1_1") (pintype "passive"))
      (node (ref "R9") (pin "1") (pinfunction "1_1") (pintype "passive"))
      (node (ref "U4") (pin "61") (pinfunction "BIASINV_61") (pintype "input"))
    )
    (net (code "26") (name "/BIAS_OUT") (class "Default")
      (node (ref "C14") (pin "2") (pinfunction "2_2") (pintype "passive"))
      (node (ref "JP1") (pin "2") (pinfunction "2_2") (pintype "passive"))
      (node (ref "R10") (pin "2") (pinfunction "2_2") (pintype "passive"))
      (node (ref "R9") (pin "2") (pinfunction "2_2") (pintype "passive"))
      (node (ref "U4") (pin "63") (pinfunction "BIASOUT_63") (pintype "output"))
    )
    (net (code "27") (name "/CLKSEL") (class "Default")
      (node (ref "R29") (pin "1") (pinfunction "1_1") (pintype "passive"))
      (node (ref "U4") (pin "52") (pinfunction "CLKSEL_52") (pintype "input"))
    )
    (net (code "28") (name "/CS") (class "Default")
      (node (ref "R28") (pin "1") (pinfunction "1_1") (pintype "passive"))
      (node (ref "U4") (pin "39") (pinfunction "~{CS}_39") (pintype "input"))
      (node (ref "U5") (pin "18") (pinfunction "IO10_18") (pintype "bidirectional"))
    )
    (net (code "29") (name "/DRDY") (class "Default")
      (node (ref "U4") (pin "47") (pinfunction "~{DRDY}_47") (pintype "output"))
      (node (ref "U5") (pin "17") (pinfunction "IO9_17") (pintype "input"))
    )
    (net (code "30") (name "/EN") (class "Default")
      (node (ref "C11") (pin "1") (pinfunction "1_1") (pintype "passive"))
      (node (ref "R7") (pin "2") (pinfunction "2_2") (pintype "passive"))
      (node (ref "SW2") (pin "1_1-") (pinfunction "1_1-_1_1-") (pintype "passive"))
      (node (ref "U5") (pin "3") (pinfunction "EN_3") (pintype "input"))
    )
    (net (code "31") (name "/GPIO0") (class "Default")
      (node (ref "R8") (pin "2") (pinfunction "2_2") (pintype "passive"))
      (node (ref "SW3") (pin "1_1-") (pinfunction "1_1-_1_1-") (pintype "passive"))
      (node (ref "U5") (pin "27") (pinfunction "IO0_27") (pintype "bidirectional"))
    )
    (net (code "32") (name "/GPIO4") (class "Default")
      (node (ref "U5") (pin "4") (pinfunction "IO4_4") (pintype "bidirectional+no_connect"))
    )
    (net (code "33") (name "/GPIO5") (class "Default")
      (node (ref "U5") (pin "5") (pinfunction "IO5_5") (pintype "bidirectional+no_connect"))
    )
    (net (code "34") (name "/IN1N") (class "Default")
      (node (ref "C30") (pin "1") (pinfunction "1_1") (pintype "passive"))
      (node (ref "R25") (pin "2") (pinfunction "2_2") (pintype "passive"))
      (node (ref "U4") (pin "15") (pinfunction "IN1N_15") (pintype "input"))
    )
    (net (code "35") (name "/IN1P") (class "Default")
      (node (ref "C15") (pin "1") (pinfunction "1_1") (pintype "passive"))
      (node (ref "R26") (pin "2") (pinfunction "2_2") (pintype "passive"))
      (node (ref "U4") (pin "16") (pinfunction "IN1P_16") (pintype "input"))
    )
    (net (code "36") (name "/IN2N") (class "Default")
      (node (ref "C28") (pin "1") (pinfunction "1_1") (pintype "passive"))
      (node (ref "R23") (pin "2") (pinfunction "2_2") (pintype "passive"))
      (node (ref "U4") (pin "13") (pinfunction "IN2N_13") (pintype "input"))
    )
    (net (code "37") (name "/IN2P") (class "Default")
      (node (ref "C29") (pin "1") (pinfunction "1_1") (pintype "passive"))
      (node (ref "R24") (pin "2") (pinfunction "2_2") (pintype "passive"))
      (node (ref "U4") (pin "14") (pinfunction "IN2P_14") (pintype "input"))
    )
    (net (code "38") (name "/IN3N") (class "Default")
      (node (ref "C26") (pin "1") (pinfunction "1_1") (pintype "passive"))
      (node (ref "R21") (pin "2") (pinfunction "2_2") (pintype "passive"))
      (node (ref "U4") (pin "11") (pinfunction "IN3N_11") (pintype "input"))
    )
    (net (code "39") (name "/IN3P") (class "Default")
      (node (ref "C27") (pin "1") (pinfunction "1_1") (pintype "passive"))
      (node (ref "R22") (pin "2") (pinfunction "2_2") (pintype "passive"))
      (node (ref "U4") (pin "12") (pinfunction "IN3P_12") (pintype "input"))
    )
    (net (code "40") (name "/IN4N") (class "Default")
      (node (ref "C24") (pin "1") (pinfunction "1_1") (pintype "passive"))
      (node (ref "R19") (pin "2") (pinfunction "2_2") (pintype "passive"))
      (node (ref "U4") (pin "9") (pinfunction "IN4N_9") (pintype "input"))
    )
    (net (code "41") (name "/IN4P") (class "Default")
      (node (ref "C25") (pin "1") (pinfunction "1_1") (pintype "passive"))
      (node (ref "R20") (pin "2") (pinfunction "2_2") (pintype "passive"))
      (node (ref "U4") (pin "10") (pinfunction "IN4P_10") (pintype "input"))
    )
    (net (code "42") (name "/IN5N") (class "Default")
      (node (ref "C22") (pin "1") (pinfunction "1_1") (pintype "passive"))
      (node (ref "R17") (pin "2") (pinfunction "2_2") (pintype "passive"))
      (node (ref "U4") (pin "7") (pinfunction "IN5N_7") (pintype "input"))
    )
    (net (code "43") (name "/IN5P") (class "Default")
      (node (ref "C23") (pin "1") (pinfunction "1_1") (pintype "passive"))
      (node (ref "R18") (pin "2") (pinfunction "2_2") (pintype "passive"))
      (node (ref "U4") (pin "8") (pinfunction "IN5P_8") (pintype "input"))
    )
    (net (code "44") (name "/IN6N") (class "Default")
      (node (ref "C20") (pin "1") (pinfunction "1_1") (pintype "passive"))
      (node (ref "R15") (pin "2") (pinfunction "2_2") (pintype "passive"))
      (node (ref "U4") (pin "5") (pinfunction "IN6N_5") (pintype "input"))
    )
    (net (code "45") (name "/IN6P") (class "Default")
      (node (ref "C21") (pin "1") (pinfunction "1_1") (pintype "passive"))
      (node (ref "R16") (pin "2") (pinfunction "2_2") (pintype "passive"))
      (node (ref "U4") (pin "6") (pinfunction "IN6P_6") (pintype "input"))
    )
    (net (code "46") (name "/IN7N") (class "Default")
      (node (ref "C18") (pin "1") (pinfunction "1_1") (pintype "passive"))
      (node (ref "R13") (pin "2") (pinfunction "2_2") (pintype "passive"))
      (node (ref "U4") (pin "3") (pinfunction "IN7N_3") (pintype "input"))
    )
    (net (code "47") (name "/IN7P") (class "Default")
      (node (ref "C19") (pin "1") (pinfunction "1_1") (pintype "passive"))
      (node (ref "R14") (pin "2") (pinfunction "2_2") (pintype "passive"))
      (node (ref "U4") (pin "4") (pinfunction "IN7P_4") (pintype "input"))
    )
    (net (code "48") (name "/IN8N") (class "Default")
      (node (ref "C16") (pin "1") (pinfunction "1_1") (pintype "passive"))
      (node (ref "R11") (pin "2") (pinfunction "2_2") (pintype "passive"))
      (node (ref "U4") (pin "1") (pinfunction "IN8N_1") (pintype "input"))
    )
    (net (code "49") (name "/IN8P") (class "Default")
      (node (ref "C17") (pin "1") (pinfunction "1_1") (pintype "passive"))
      (node (ref "R12") (pin "2") (pinfunction "2_2") (pintype "passive"))
      (node (ref "U4") (pin "2") (pinfunction "IN8P_2") (pintype "input"))
    )
    (net (code "50") (name "/MISO") (class "Default")
      (node (ref "U4") (pin "43") (pinfunction "DOUT_43") (pintype "tri_state"))
      (node (ref "U5") (pin "21") (pinfunction "IO13_21") (pintype "bidirectional"))
    )
    (net (code "51") (name "/MOSI") (class "Default")
      (node (ref "U4") (pin "34") (pinfunction "DIN_34") (pintype "input"))
      (node (ref "U5") (pin "19") (pinfunction "IO11_19") (pintype "bidirectional"))
    )
    (net (code "52") (name "/PWDN") (class "Default")
      (node (ref "R31") (pin "1") (pinfunction "1_1") (pintype "passive"))
      (node (ref "U4") (pin "35") (pinfunction "~{PWDN}_35") (pintype "input"))
      (node (ref "U5") (pin "23") (pinfunction "IO21_23") (pintype "bidirectional"))
    )
    (net (code "53") (name "/REF") (class "Default")
      (node (ref "D5") (pin "4") (pinfunction "IO3_4") (pintype "bidirectional"))
      (node (ref "J3J") (pin "1") (pinfunction "1_1") (pintype "passive"))
      (node (ref "R27") (pin "1") (pinfunction "1_1") (pintype "passive"))
    )
    (net (code "54") (name "/RXD") (class "Default")
      (node (ref "J5") (pin "2") (pinfunction "2_2") (pintype "passive"))
      (node (ref "U5") (pin "36") (pinfunction "RXD0_36") (pintype "bidirectional"))
    )
    (net (code "55") (name "/SCLK") (class "Default")
      (node (ref "U4") (pin "40") (pinfunction "SCLK_40") (pintype "input"))
      (node (ref "U5") (pin "20") (pinfunction "IO12_20") (pintype "bidirectional"))
    )
    (net (code "56") (name "/SRB1") (class "Default")
      (node (ref "C31") (pin "1") (pinfunction "1_1") (pintype "passive"))
      (node (ref "R27") (pin "2") (pinfunction "2_2") (pintype "passive"))
      (node (ref "U4") (pin "17") (pinfunction "SRB1_17") (pintype "input"))
    )
    (net (code "57") (name "/SRB2") (class "Default")
      (node (ref "D5") (pin "5") (pinfunction "IO4_5") (pintype "bidirectional"))
      (node (ref "J3J") (pin "2") (pinfunction "2_2") (pintype "passive"))
      (node (ref "U4") (pin "18") (pinfunction "SRB2_18") (pintype "input"))
    )
    (net (code "58") (name "/TXD") (class "Default")
      (node (ref "J5") (pin "1") (pinfunction "1_1") (pintype "passive"))
      (node (ref "U5") (pin "37") (pinfunction "TXD0_37") (pintype "bidirectional"))
    )
    (net (code "59") (name "/USB_D_N") (class "Default")
      (node (ref "J2") (pin "A7") (pinfunction "Dn1_A7") (pintype "bidirectional"))
      (node (ref "J2") (pin "B7") (pinfunction "Dn2_B7") (pintype "bidirectional"))
      (node (ref "U5") (pin "13") (pinfunction "IO19_13") (pintype "bidirectional"))
    )
    (net (code "60") (name "/USB_D_P") (class "Default")
      (node (ref "J2") (pin "A6") (pinfunction "Dp1_A6") (pintype "bidirectional"))
      (node (ref "J2") (pin "B6") (pinfunction "Dp2_B6") (pintype "bidirectional"))
      (node (ref "U5") (pin "14") (pinfunction "IO20_14") (pintype "bidirectional"))
    )
    (net (code "61") (name "/VCAP1") (class "Default")
      (node (ref "C34") (pin "2") (pinfunction "2_2") (pintype "passive"))
      (node (ref "U4") (pin "28") (pinfunction "VCAP1_28") (pintype "passive"))
    )
    (net (code "62") (name "/VCAP2") (class "Default")
      (node (ref "C35") (pin "1") (pinfunction "1_1") (pintype "passive"))
      (node (ref "U4") (pin "30") (pinfunction "VCAP2_30") (pintype "passive"))
    )
    (net (code "63") (name "/VCAP3") (class "Default")
      (node (ref "C36") (pin "1") (pinfunction "1_1") (pintype "passive"))
      (node (ref "C37") (pin "2") (pinfunction "2_2") (pintype "passive"))
      (node (ref "U4") (pin "55") (pinfunction "VCAP3_55") (pintype "passive"))
    )
    (net (code "64") (name "/VCAP4") (class "Default")
      (node (ref "C38") (pin "1") (pinfunction "1_1") (pintype "passive"))
      (node (ref "U4") (pin "26") (pinfunction "VCAP4_26") (pintype "passive"))
    )
    (net (code "65") (name "/VREFP") (class "Default")
      (node (ref "C32") (pin "2") (pinfunction "2_2") (pintype "passive"))
      (node (ref "C33") (pin "1") (pinfunction "1_1") (pintype "passive"))
      (node (ref "U4") (pin "24") (pinfunction "VREFP_24") (pintype "passive"))
    )
    (net (code "66") (name "3v3") (class "Default")
      (node (ref "C12") (pin "1") (pinfunction "1_1") (pintype "passive"))
      (node (ref "C13") (pin "1") (pinfunction "1_1") (pintype "passive"))
      (node (ref "C7") (pin "1") (pinfunction "1_1") (pintype "passive"))
      (node (ref "R7") (pin "1") (pinfunction "1_1") (pintype "passive"))
      (node (ref "R8") (pin "1") (pinfunction "1_1") (pintype "passive"))
      (node (ref "TP5") (pin "1") (pinfunction "TP_1") (pintype "passive"))
      (node (ref "U2") (pin "5") (pinfunction "OUT_5") (pintype "power_in"))
      (node (ref "U5") (pin "2") (pinfunction "3V3_2") (pintype "power_in"))
    )
    (net (code "67") (name "AVDD") (class "Default")
      (node (ref "C39") (pin "1") (pinfunction "1_1") (pintype "passive"))
      (node (ref "C4") (pin "1") (pinfunction "1_1") (pintype "passive"))
      (node (ref "C40") (pin "1") (pinfunction "1_1") (pintype "passive"))
      (node (ref "C41") (pin "2") (pinfunction "2_2") (pintype "passive"))
      (node (ref "C44") (pin "1") (pinfunction "1_1") (pintype "passive"))
      (node (ref "C45") (pin "2") (pinfunction "2_2") (pintype "passive"))
      (node (ref "R1") (pin "1") (pinfunction "1_1") (pintype "passive"))
      (node (ref "TP2") (pin "1") (pinfunction "TP_1") (pintype "passive"))
      (node (ref "U1") (pin "11") (pinfunction "OUT+_11") (pintype "passive"))
      (node (ref "U4") (pin "19") (pinfunction "AVDD_19") (pintype "power_in"))
      (node (ref "U4") (pin "21") (pinfunction "AVDD_21") (pintype "power_in"))
      (node (ref "U4") (pin "22") (pinfunction "AVDD_22") (pintype "power_in"))
      (node (ref "U4") (pin "54") (pinfunction "AVDD1_54") (pintype "power_in"))
      (node (ref "U4") (pin "56") (pinfunction "AVDD_56") (pintype "power_in"))
      (node (ref "U4") (pin "59") (pinfunction "AVDD_59") (pintype "power_in"))
    )
    (net (code "68") (name "AVSS") (class "Default")
      (node (ref "C32") (pin "1") (pinfunction "1_1") (pintype "passive"))
      (node (ref "C33") (pin "2") (pinfunction "2_2") (pintype "passive"))
      (node (ref "C34") (pin "1") (pinfunction "1_1") (pintype "passive"))
      (node (ref "C35") (pin "2") (pinfunction "2_2") (pintype "passive"))
      (node (ref "C36") (pin "2") (pinfunction "2_2") (pintype "passive"))
      (node (ref "C37") (pin "1") (pinfunction "1_1") (pintype "passive"))
      (node (ref "C38") (pin "2") (pinfunction "2_2") (pintype "passive"))
      (node (ref "C39") (pin "2") (pinfunction "2_2") (pintype "passive"))
      (node (ref "C42") (pin "2") (pinfunction "2_2") (pintype "passive"))
      (node (ref "C43") (pin "1") (pinfunction "1_1") (pintype "passive"))
      (node (ref "C44") (pin "2") (pinfunction "2_2") (pintype "passive"))
      (node (ref "C45") (pin "1") (pinfunction "1_1") (pintype "passive"))
      (node (ref "C5") (pin "2") (pinfunction "2_2") (pintype "passive"))
      (node (ref "R3") (pin "2") (pinfunction "2_2") (pintype "passive"))
      (node (ref "TP3") (pin "1") (pinfunction "TP_1") (pintype "passive"))
      (node (ref "U1") (pin "6") (pinfunction "OUT-_6") (pintype "passive"))
      (node (ref "U4") (pin "20") (pinfunction "AVSS_20") (pintype "power_in"))
      (node (ref "U4") (pin "23") (pinfunction "AVSS_23") (pintype "power_in"))
      (node (ref "U4") (pin "25") (pinfunction "VREFN_25") (pintype "passive"))
      (node (ref "U4") (pin "32") (pinfunction "AVSS_32") (pintype "power_in"))
      (node (ref "U4") (pin "53") (pinfunction "AVSS1_53") (pintype "power_in"))
      (node (ref "U4") (pin "57") (pinfunction "AVSS_57") (pintype "power_in"))
      (node (ref "U4") (pin "58") (pinfunction "AVSS_58") (pintype "power_in"))
      (node (ref "U4") (pin "60") (pinfunction "BIASREF_60") (pintype "input"))
    )
    (net (code "69") (name "DVDD") (class "Default")
      (node (ref "C46") (pin "1") (pinfunction "1_1") (pintype "passive"))
      (node (ref "C47") (pin "2") (pinfunction "2_2") (pintype "passive"))
      (node (ref "C9") (pin "1") (pinfunction "1_1") (pintype "passive"))
      (node (ref "R28") (pin "2") (pinfunction "2_2") (pintype "passive"))
      (node (ref "R29") (pin "2") (pinfunction "2_2") (pintype "passive"))
      (node (ref "R30") (pin "2") (pinfunction "2_2") (pintype "passive"))
      (node (ref "R31") (pin "2") (pinfunction "2_2") (pintype "passive"))
      (node (ref "TP4") (pin "1") (pinfunction "TP_1") (pintype "passive"))
      (node (ref "U3") (pin "5") (pinfunction "OUT_5") (pintype "passive"))
      (node (ref "U4") (pin "48") (pinfunction "DVDD_48") (pintype "power_in"))
      (node (ref "U4") (pin "50") (pinfunction "DVDD_50") (pintype "power_in"))
    )
    (net (code "70") (name "GND") (class "Default")
      (node (ref "C10") (pin "2") (pinfunction "2_2") (pintype "passive"))
      (node (ref "C11") (pin "2") (pinfunction "2_2") (pintype "passive"))
      (node (ref "C12") (pin "2") (pinfunction "2_2") (pintype "passive"))
      (node (ref "C13") (pin "2") (pinfunction "2_2") (pintype "passive"))
      (node (ref "C15") (pin "2") (pinfunction "2_2") (pintype "passive"))
      (node (ref "C16") (pin "2") (pinfunction "2_2") (pintype "passive"))
      (node (ref "C17") (pin "2") (pinfunction "2_2") (pintype "passive"))
      (node (ref "C18") (pin "2") (pinfunction "2_2") (pintype "passive"))
      (node (ref "C19") (pin "2") (pinfunction "2_2") (pintype "passive"))
      (node (ref "C2") (pin "2") (pinfunction "2_2") (pintype "passive"))
      (node (ref "C20") (pin "2") (pinfunction "2_2") (pintype "passive"))
      (node (ref "C21") (pin "2") (pinfunction "2_2") (pintype "passive"))
      (node (ref "C22") (pin "2") (pinfunction "2_2") (pintype "passive"))
      (node (ref "C23") (pin "2") (pinfunction "2_2") (pintype "passive"))
      (node (ref "C24") (pin "2") (pinfunction "2_2") (pintype "passive"))
      (node (ref "C25") (pin "2") (pinfunction "2_2") (pintype "passive"))
      (node (ref "C26") (pin "2") (pinfunction "2_2") (pintype "passive"))
      (node (ref "C27") (pin "2") (pinfunction "2_2") (pintype "passive"))
      (node (ref "C28") (pin "2") (pinfunction "2_2") (pintype "passive"))
      (node (ref "C29") (pin "2") (pinfunction "2_2") (pintype "passive"))
      (node (ref "C3") (pin "2") (pinfunction "2_2") (pintype "passive"))
      (node (ref "C30") (pin "2") (pinfunction "2_2") (pintype "passive"))
      (node (ref "C31") (pin "2") (pinfunction "2_2") (pintype "passive"))
      (node (ref "C4") (pin "2") (pinfunction "2_2") (pintype "passive"))
      (node (ref "C40") (pin "2") (pinfunction "2_2") (pintype "passive"))
      (node (ref "C41") (pin "1") (pinfunction "1_1") (pintype "passive"))
      (node (ref "C42") (pin "1") (pinfunction "1_1") (pintype "passive"))
      (node (ref "C43") (pin "2") (pinfunction "2_2") (pintype "passive"))
      (node (ref "C46") (pin "2") (pinfunction "2_2") (pintype "passive"))
      (node (ref "C47") (pin "1") (pinfunction "1_1") (pintype "passive"))
      (node (ref "C48") (pin "2") (pinfunction "2_2") (pintype "passive"))
      (node (ref "C49") (pin "2") (pinfunction "2_2") (pintype "passive"))
      (node (ref "C5") (pin "1") (pinfunction "1_1") (pintype "passive"))
      (node (ref "C6") (pin "2") (pinfunction "2_2") (pintype "passive"))
      (node (ref "C7") (pin "2") (pinfunction "2_2") (pintype "passive"))
      (node (ref "C9") (pin "2") (pinfunction "2_2") (pintype "passive"))
      (node (ref "D1") (pin "3") (pinfunction "GND_3") (pintype "power_in"))
      (node (ref "D2") (pin "3") (pinfunction "GND_3") (pintype "power_in"))
      (node (ref "D3") (pin "3") (pinfunction "GND_3") (pintype "power_in"))
      (node (ref "D4") (pin "3") (pinfunction "GND_3") (pintype "power_in"))
      (node (ref "D5") (pin "3") (pinfunction "GND_3") (pintype "power_in"))
      (node (ref "D6") (pin "2") (pinfunction "A_2") (pintype "passive"))
      (node (ref "D7") (pin "2") (pinfunction "A_2") (pintype "passive"))
      (node (ref "J1") (pin "1") (pinfunction "1_1") (pintype "power_in"))
      (node (ref "J2") (pin "1") (pinfunction "MNT_1_1") (pintype "passive"))
      (node (ref "J2") (pin "2") (pinfunction "MNT_2_2") (pintype "passive"))
      (node (ref "J2") (pin "3") (pinfunction "MNT_3_3") (pintype "power_in"))
      (node (ref "J2") (pin "4") (pinfunction "MNT_4_4") (pintype "power_in"))
      (node (ref "J2") (pin "A1-B12") (pinfunction "GND_A1-B12") (pintype "power_in"))
      (node (ref "J2") (pin "B1-A12") (pinfunction "GND_B1-A12") (pintype "power_in"))
      (node (ref "J3A") (pin "2") (pinfunction "2_2") (pintype "passive"))
      (node (ref "J5") (pin "3") (pinfunction "3_3") (pintype "passive"))
      (node (ref "R2") (pin "2") (pinfunction "2_2") (pintype "passive"))
      (node (ref "R32") (pin "2") (pinfunction "2_2") (pintype "passive"))
      (node (ref "R33") (pin "2") (pinfunction "2_2") (pintype "passive"))
      (node (ref "R34") (pin "2") (pinfunction "2_2") (pintype "passive"))
      (node (ref "R35") (pin "2") (pinfunction "2_2") (pintype "passive"))
      (node (ref "R4") (pin "1") (pinfunction "1_1") (pintype "passive"))
      (node (ref "R5") (pin "2") (pinfunction "2_2") (pintype "passive"))
      (node (ref "R6") (pin "2") (pinfunction "2_2") (pintype "passive"))
      (node (ref "SW2") (pin "2_2+") (pinfunction "2_2+_2_2+") (pintype "passive"))
      (node (ref "SW3") (pin "2_2+") (pinfunction "2_2+_2_2+") (pintype "passive"))
      (node (ref "TP1") (pin "1") (pinfunction "1_1") (pintype "passive"))
      (node (ref "U1") (pin "1") (pinfunction "PGOOD_1") (pintype "open_collector"))
      (node (ref "U1") (pin "13") (pinfunction "Thermal_Pad_13") (pintype "passive"))
      (node (ref "U1") (pin "4") (pinfunction "GND_4") (pintype "power_in"))
      (node (ref "U2") (pin "2") (pinfunction "GND_2") (pintype "power_in"))
      (node (ref "U2") (pin "4") (pinfunction "NC_4") (pintype "passive"))
      (node (ref "U3") (pin "2") (pinfunction "GND_2") (pintype "power_in"))
      (node (ref "U3") (pin "4") (pinfunction "NC_4") (pintype "passive"))
      (node (ref "U4") (pin "31") (pinfunction "RESV1_31") (pintype "power_in"))
      (node (ref "U4") (pin "33") (pinfunction "DGND_33") (pintype "power_in"))
      (node (ref "U4") (pin "41") (pinfunction "DAISY_IN_41") (pintype "input"))
      (node (ref "U4") (pin "49") (pinfunction "DGND_49") (pintype "power_in"))
      (node (ref "U4") (pin "51") (pinfunction "DGND_51") (pintype "power_in"))
      (node (ref "U5") (pin "1") (pinfunction "GND_1") (pintype "power_in"))
      (node (ref "U5") (pin "40") (pinfunction "GND_40") (pintype "power_in"))
      (node (ref "U5") (pin "41_1") (pinfunction "GND_41_1") (pintype "power_in"))
      (node (ref "U5") (pin "41_2") (pinfunction "GND_41_2") (pintype "power_in"))
      (node (ref "U5") (pin "41_3") (pinfunction "GND_41_3") (pintype "power_in"))
      (node (ref "U5") (pin "41_4") (pinfunction "GND_41_4") (pintype "power_in"))
      (node (ref "U5") (pin "41_5") (pinfunction "GND_41_5") (pintype "power_in"))
      (node (ref "U5") (pin "41_6") (pinfunction "GND_41_6") (pintype "power_in"))
      (node (ref "U5") (pin "41_7") (pinfunction "GND_41_7") (pintype "power_in"))
      (node (ref "U5") (pin "41_8") (pinfunction "GND_41_8") (pintype "power_in"))
      (node (ref "U5") (pin "41_9") (pinfunction "GND_41_9") (pintype "power_in"))
    )
    (net (code "71") (name "Net-(J2A-CC1)") (class "Default")
      (node (ref "J2") (pin "A5") (pinfunction "CC1_A5") (pintype "passive"))
      (node (ref "R5") (pin "1") (pinfunction "1_1") (pintype "passive"))
    )
    (net (code "72") (name "Net-(J2A-CC2)") (class "Default")
      (node (ref "J2") (pin "B5") (pinfunction "CC2_B5") (pintype "passive"))
      (node (ref "R6") (pin "1") (pinfunction "1_1") (pintype "passive"))
    )
    (net (code "73") (name "Net-(U1-C1+)") (class "Default")
      (node (ref "C1") (pin "1") (pinfunction "1_1") (pintype "passive"))
      (node (ref "U1") (pin "10") (pinfunction "C1+_10") (pintype "passive"))
    )
    (net (code "74") (name "Net-(U1-C1-)") (class "Default")
      (node (ref "C1") (pin "2") (pinfunction "2_2") (pintype "passive"))
      (node (ref "U1") (pin "9") (pinfunction "C1-_9") (pintype "passive"))
    )
    (net (code "75") (name "Net-(U1-CP)") (class "Default")
      (node (ref "C3") (pin "1") (pinfunction "1_1") (pintype "passive"))
      (node (ref "U1") (pin "5") (pinfunction "CP_5") (pintype "passive"))
    )
    (net (code "76") (name "Net-(U1-FB+)") (class "Default")
      (node (ref "R1") (pin "2") (pinfunction "2_2") (pintype "passive"))
      (node (ref "R2") (pin "1") (pinfunction "1_1") (pintype "passive"))
      (node (ref "U1") (pin "2") (pinfunction "FB+_2") (pintype "input"))
    )
    (net (code "77") (name "Net-(U1-FB-)") (class "Default")
      (node (ref "R3") (pin "1") (pinfunction "1_1") (pintype "passive"))
      (node (ref "R4") (pin "2") (pinfunction "2_2") (pintype "passive"))
      (node (ref "U1") (pin "7") (pinfunction "FB-_7") (pintype "input"))
    )
    (net (code "78") (name "VBAT") (class "Default")
      (node (ref "C49") (pin "1") (pinfunction "1_1") (pintype "passive"))
      (node (ref "D6") (pin "1") (pinfunction "K_1") (pintype "passive"))
      (node (ref "J1") (pin "2") (pinfunction "2_2") (pintype "power_in"))
      (node (ref "SW1") (pin "1") (pinfunction "1_1") (pintype "passive"))
    )
    (net (code "79") (name "VBUS") (class "Default")
      (node (ref "C48") (pin "1") (pinfunction "1_1") (pintype "passive"))
      (node (ref "D7") (pin "1") (pinfunction "C_1") (pintype "passive"))
      (node (ref "J2") (pin "A4-B9") (pinfunction "VBUS_A4-B9") (pintype "power_in"))
      (node (ref "J2") (pin "B4-A9") (pinfunction "VBUS_B4-A9") (pintype "power_in"))
      (node (ref "SW1") (pin "3") (pinfunction "3_3") (pintype "passive"))
    )
    (net (code "80") (name "VIN") (class "Default")
      (node (ref "C10") (pin "1") (pinfunction "1_1") (pintype "passive"))
      (node (ref "C2") (pin "1") (pinfunction "1_1") (pintype "passive"))
      (node (ref "C6") (pin "1") (pinfunction "1_1") (pintype "passive"))
      (node (ref "SW1") (pin "2") (pinfunction "COMM_2") (pintype "passive"))
      (node (ref "TP6") (pin "1") (pinfunction "TP_1") (pintype "passive"))
      (node (ref "U1") (pin "12") (pinfunction "EN+_12") (pintype "input"))
      (node (ref "U1") (pin "3") (pinfunction "VIN_3") (pintype "power_in"))
      (node (ref "U1") (pin "8") (pinfunction "EN-_8") (pintype "input"))
      (node (ref "U2") (pin "1") (pinfunction "IN_1") (pintype "input"))
      (node (ref "U2") (pin "3") (pinfunction "EN_3") (pintype "input"))
      (node (ref "U3") (pin "1") (pinfunction "IN_1") (pintype "power_in"))
      (node (ref "U3") (pin "3") (pinfunction "EN_3") (pintype "input"))
    )
    (net (code "81") (name "unconnected-(D1-IO2-Pad2)") (class "Default")
      (node (ref "D1") (pin "2") (pinfunction "IO2_2") (pintype "bidirectional+no_connect"))
    )
    (net (code "82") (name "unconnected-(D1-NC-Pad6)") (class "Default")
      (node (ref "D1") (pin "6") (pinfunction "NC_6") (pintype "passive+no_connect"))
    )
    (net (code "83") (name "unconnected-(D2-NC-Pad6)") (class "Default")
      (node (ref "D2") (pin "6") (pinfunction "NC_6") (pintype "passive+no_connect"))
    )
    (net (code "84") (name "unconnected-(D3-NC-Pad6)") (class "Default")
      (node (ref "D3") (pin "6") (pinfunction "NC_6") (pintype "passive+no_connect"))
    )
    (net (code "85") (name "unconnected-(D4-NC-Pad6)") (class "Default")
      (node (ref "D4") (pin "6") (pinfunction "NC_6") (pintype "passive+no_connect"))
    )
    (net (code "86") (name "unconnected-(D5-NC-Pad6)") (class "Default")
      (node (ref "D5") (pin "6") (pinfunction "NC_6") (pintype "passive+no_connect"))
    )
    (net (code "87") (name "unconnected-(J2A-SBU1-PadA8)") (class "Default")
      (node (ref "J2") (pin "A8") (pinfunction "SBU1_A8") (pintype "passive+no_connect"))
    )
    (net (code "88") (name "unconnected-(J2A-SBU2-PadB8)") (class "Default")
      (node (ref "J2") (pin "B8") (pinfunction "SBU2_B8") (pintype "passive+no_connect"))
    )
    (net (code "89") (name "unconnected-(SW2-Pad1_2+)") (class "Default")
      (node (ref "SW2") (pin "1_2+") (pinfunction "1_2+_1_2+") (pintype "passive"))
    )
    (net (code "90") (name "unconnected-(SW2-Pad2_1-)") (class "Default")
      (node (ref "SW2") (pin "2_1-") (pinfunction "2_1-_2_1-") (pintype "passive"))
    )
    (net (code "91") (name "unconnected-(SW3-Pad1_2+)") (class "Default")
      (node (ref "SW3") (pin "1_2+") (pinfunction "1_2+_1_2+") (pintype "passive"))
    )
    (net (code "92") (name "unconnected-(SW3-Pad2_1-)") (class "Default")
      (node (ref "SW3") (pin "2_1-") (pinfunction "2_1-_2_1-") (pintype "passive"))
    )
    (net (code "93") (name "unconnected-(U4A-CLK-Pad37)") (class "Default")
      (node (ref "U4") (pin "37") (pinfunction "CLK_37") (pintype "bidirectional+no_connect"))
    )
    (net (code "94") (name "unconnected-(U4A-NC-Pad27)") (class "Default")
      (node (ref "U4") (pin "27") (pinfunction "NC_27") (pintype "passive+no_connect"))
    )
    (net (code "95") (name "unconnected-(U4A-NC-Pad29)") (class "Default")
      (node (ref "U4") (pin "29") (pinfunction "NC_29") (pintype "passive+no_connect"))
    )
    (net (code "96") (name "unconnected-(U4A-RESERVED-Pad64)") (class "Default")
      (node (ref "U4") (pin "64") (pinfunction "RESERVED_64") (pintype "passive+no_connect"))
    )
    (net (code "97") (name "unconnected-(U5-IO1-Pad39)") (class "Default")
      (node (ref "U5") (pin "39") (pinfunction "IO1_39") (pintype "bidirectional+no_connect"))
    )
    (net (code "98") (name "unconnected-(U5-IO2-Pad38)") (class "Default")
      (node (ref "U5") (pin "38") (pinfunction "IO2_38") (pintype "bidirectional+no_connect"))
    )
    (net (code "99") (name "unconnected-(U5-IO3-Pad15)") (class "Default")
      (node (ref "U5") (pin "15") (pinfunction "IO3_15") (pintype "bidirectional+no_connect"))
    )
    (net (code "100") (name "unconnected-(U5-IO6-Pad6)") (class "Default")
      (node (ref "U5") (pin "6") (pinfunction "IO6_6") (pintype "bidirectional+no_connect"))
    )
    (net (code "101") (name "unconnected-(U5-IO7-Pad7)") (class "Default")
      (node (ref "U5") (pin "7") (pinfunction "IO7_7") (pintype "bidirectional+no_connect"))
    )
    (net (code "102") (name "unconnected-(U5-IO8-Pad12)") (class "Default")
      (node (ref "U5") (pin "12") (pinfunction "IO8_12") (pintype "bidirectional+no_connect"))
    )
    (net (code "103") (name "unconnected-(U5-IO15-Pad8)") (class "Default")
      (node (ref "U5") (pin "8") (pinfunction "IO15_8") (pintype "bidirectional+no_connect"))
    )
    (net (code "104") (name "unconnected-(U5-IO16-Pad9)") (class "Default")
      (node (ref "U5") (pin "9") (pinfunction "IO16_9") (pintype "bidirectional+no_connect"))
    )
    (net (code "105") (name "unconnected-(U5-IO17-Pad10)") (class "Default")
      (node (ref "U5") (pin "10") (pinfunction "IO17_10") (pintype "bidirectional+no_connect"))
    )
    (net (code "106") (name "unconnected-(U5-IO35-Pad28)") (class "Default")
      (node (ref "U5") (pin "28") (pinfunction "IO35_28") (pintype "bidirectional+no_connect"))
    )
    (net (code "107") (name "unconnected-(U5-IO36-Pad29)") (class "Default")
      (node (ref "U5") (pin "29") (pinfunction "IO36_29") (pintype "bidirectional+no_connect"))
    )
    (net (code "108") (name "unconnected-(U5-IO37-Pad30)") (class "Default")
      (node (ref "U5") (pin "30") (pinfunction "IO37_30") (pintype "bidirectional+no_connect"))
    )
    (net (code "109") (name "unconnected-(U5-IO38-Pad31)") (class "Default")
      (node (ref "U5") (pin "31") (pinfunction "IO38_31") (pintype "bidirectional+no_connect"))
    )
    (net (code "110") (name "unconnected-(U5-IO39-Pad32)") (class "Default")
      (node (ref "U5") (pin "32") (pinfunction "IO39_32") (pintype "bidirectional+no_connect"))
    )
    (net (code "111") (name "unconnected-(U5-IO40-Pad33)") (class "Default")
      (node (ref "U5") (pin "33") (pinfunction "IO40_33") (pintype "bidirectional+no_connect"))
    )
    (net (code "112") (name "unconnected-(U5-IO41-Pad34)") (class "Default")
      (node (ref "U5") (pin "34") (pinfunction "IO41_34") (pintype "bidirectional+no_connect"))
    )
    (net (code "113") (name "unconnected-(U5-IO42-Pad35)") (class "Default")
      (node (ref "U5") (pin "35") (pinfunction "IO42_35") (pintype "bidirectional+no_connect"))
    )
    (net (code "114") (name "unconnected-(U5-IO45-Pad26)") (class "Default")
      (node (ref "U5") (pin "26") (pinfunction "IO45_26") (pintype "bidirectional+no_connect"))
    )
    (net (code "115") (name "unconnected-(U5-IO46-Pad16)") (class "Default")
      (node (ref "U5") (pin "16") (pinfunction "IO46_16") (pintype "bidirectional+no_connect"))
    )
    (net (code "116") (name "unconnected-(U5-IO47-Pad24)") (class "Default")
      (node (ref "U5") (pin "24") (pinfunction "IO47_24") (pintype "bidirectional+no_connect"))
    )
    (net (code "117") (name "unconnected-(U5-IO48-Pad25)") (class "Default")
      (node (ref "U5") (pin "25") (pinfunction "IO48_25") (pintype "bidirectional+no_connect"))
    )
  )
)
